# Hive_1_4.net
KiCad netlist of a schematic drawn in EAGLE
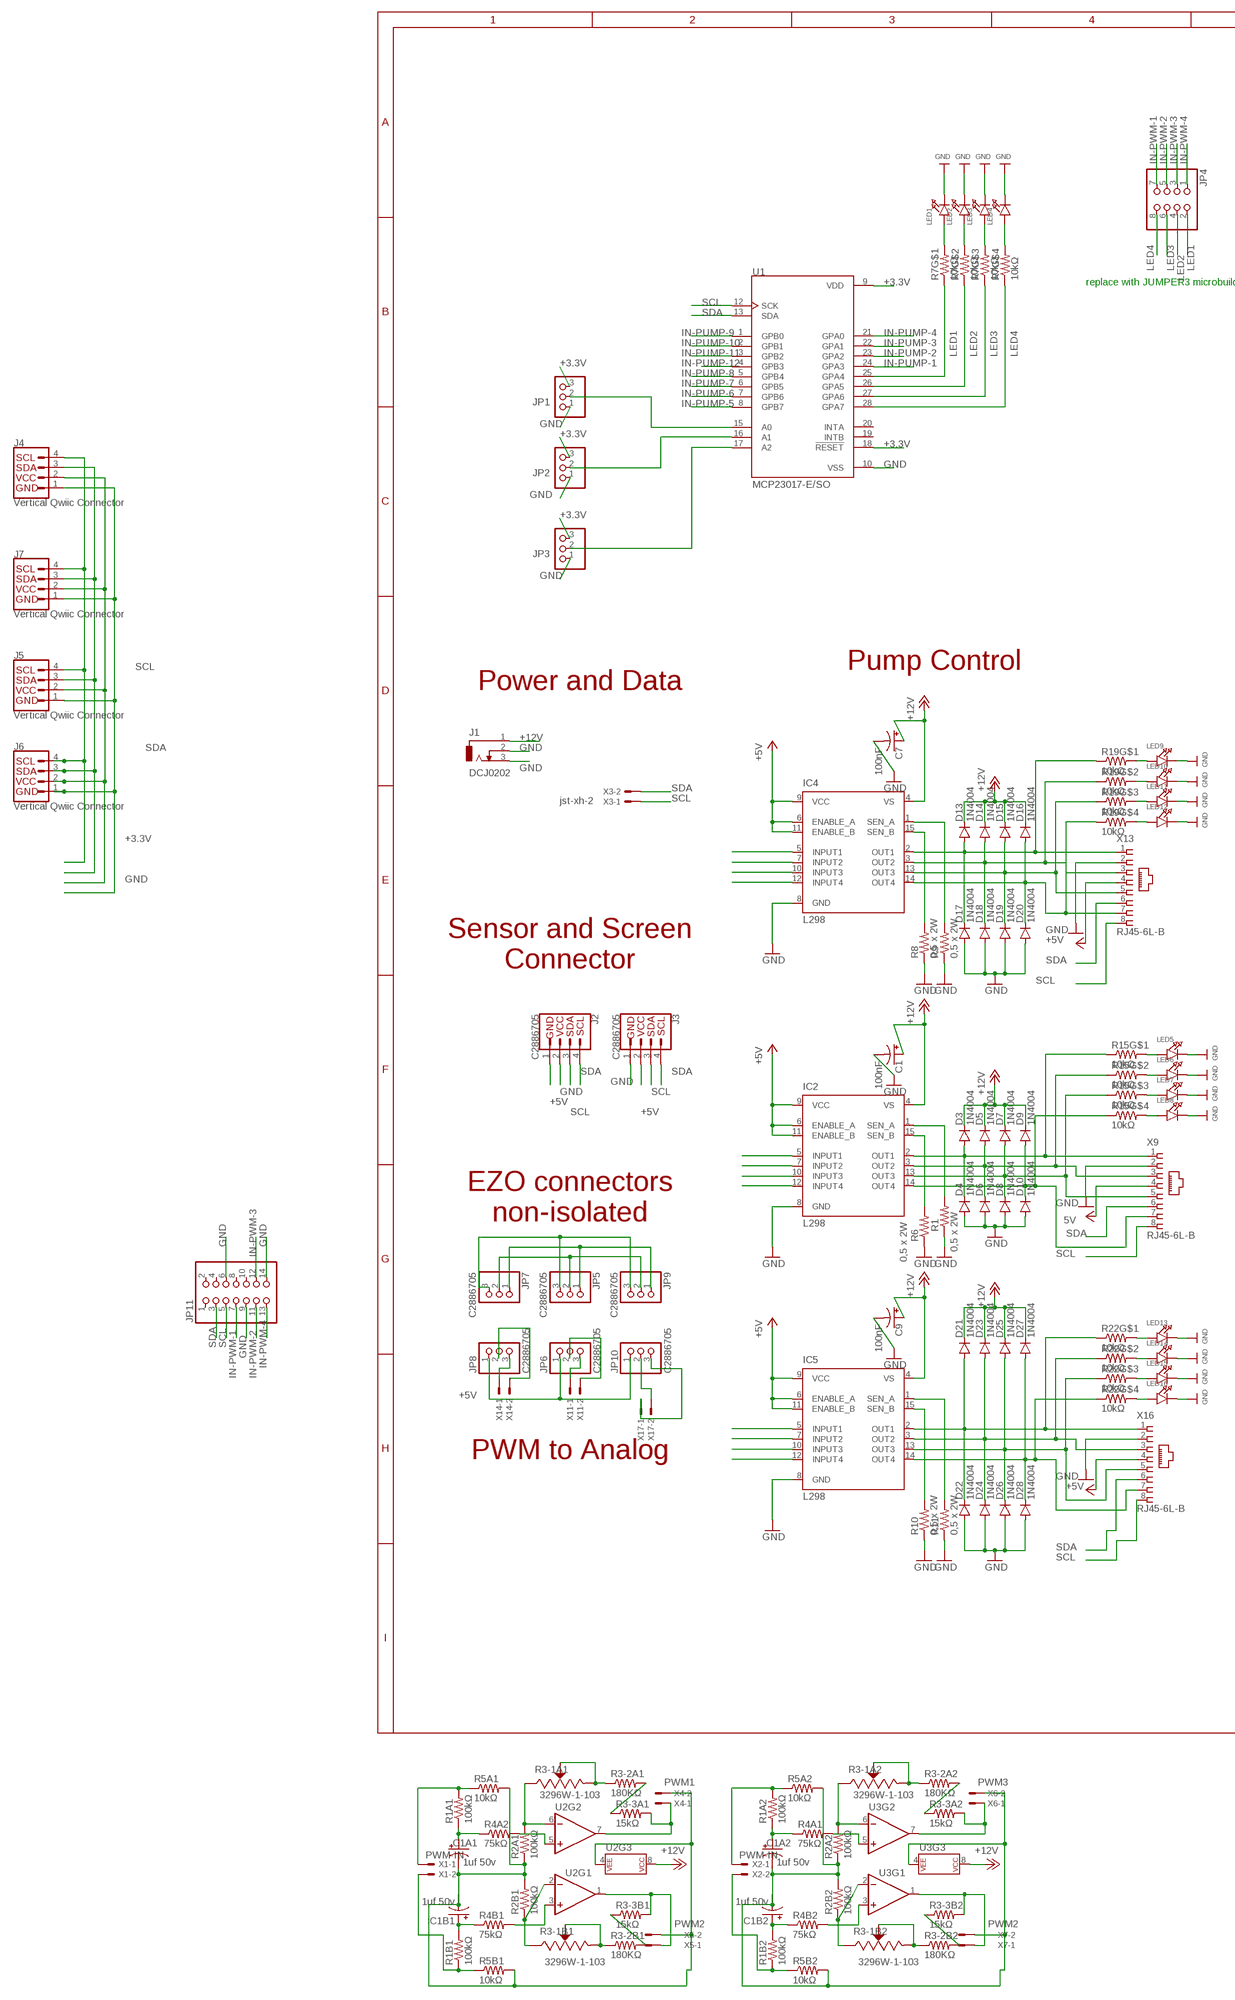
[diagram p0: schematic, sheet 1, part 1 of 2]
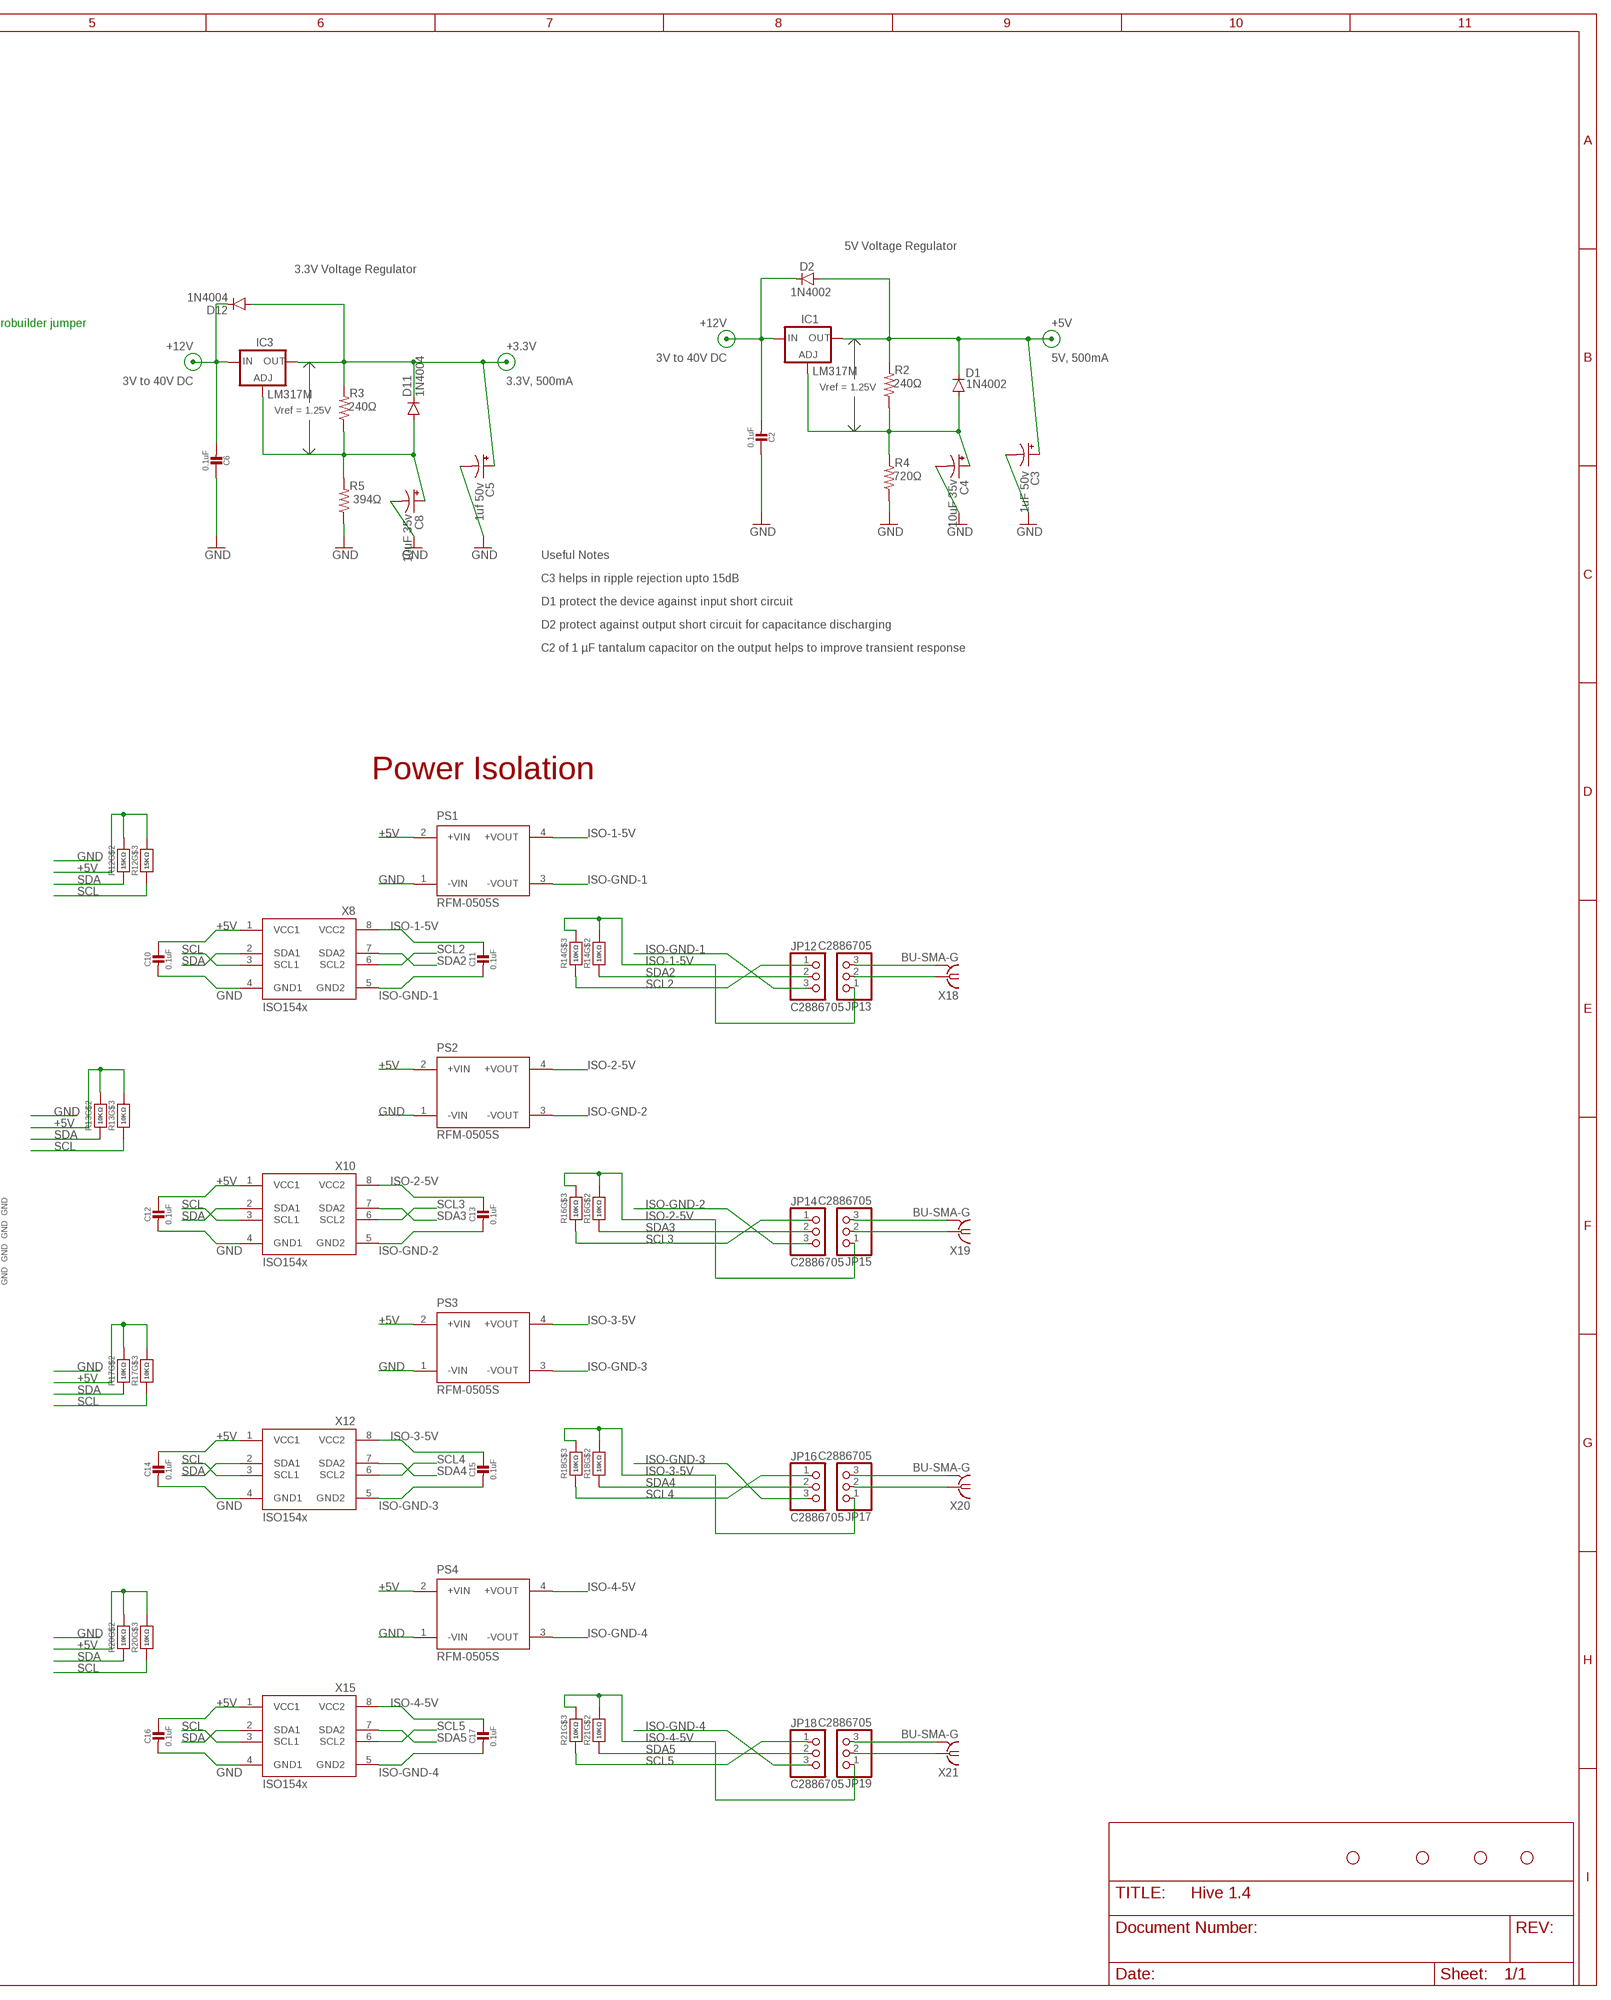
[diagram p1: schematic, sheet 1, part 2 of 2]

(export (version "E")
  (design (tool "Eeschema 10.0.6"))
  (components
    (comp (ref "C1")
      (value "100nF")
      (footprint "eagle-import:UD-4X5,8_NICHICON")
      (libsource (lib "eagle-import") (part "CPOL-USUD-4X5,8"))
    )
    (comp (ref "C1A1")
      (value "1uf 50v")
      (footprint "eagle-import:UD-4X5,8_NICHICON")
      (libsource (lib "eagle-import") (part "CPOL-USUD-4X5,8"))
    )
    (comp (ref "C1A2")
      (value "1uf 50v")
      (footprint "eagle-import:UD-4X5,8_NICHICON")
      (libsource (lib "eagle-import") (part "CPOL-USUD-4X5,8"))
    )
    (comp (ref "C1B1")
      (value "1uf 50v")
      (footprint "eagle-import:UD-4X5,8_NICHICON")
      (libsource (lib "eagle-import") (part "CPOL-USUD-4X5,8"))
    )
    (comp (ref "C1B2")
      (value "1uf 50v")
      (footprint "eagle-import:UD-4X5,8_NICHICON")
      (libsource (lib "eagle-import") (part "CPOL-USUD-4X5,8"))
    )
    (comp (ref "C2")
      (value "0.1uF")
      (footprint "eagle-import:0603-NO")
      (libsource (lib "eagle-import") (part "CAP_CERAMIC0603_NO"))
    )
    (comp (ref "C3")
      (value "1uF 50v")
      (footprint "eagle-import:UD-4X5,8_NICHICON")
      (libsource (lib "eagle-import") (part "CPOL-USUD-4X5,8"))
    )
    (comp (ref "C4")
      (value "10uF 35v")
      (footprint "eagle-import:UD-4X5,8_NICHICON")
      (libsource (lib "eagle-import") (part "CPOL-USUD-4X5,8"))
    )
    (comp (ref "C5")
      (value "1uf 50v")
      (footprint "eagle-import:UD-4X5,8_NICHICON")
      (libsource (lib "eagle-import") (part "CPOL-USUD-4X5,8"))
    )
    (comp (ref "C6")
      (value "0.1uF")
      (footprint "eagle-import:0603-NO")
      (libsource (lib "eagle-import") (part "CAP_CERAMIC0603_NO"))
    )
    (comp (ref "C7")
      (value "100nF")
      (footprint "eagle-import:UD-4X5,8_NICHICON")
      (libsource (lib "eagle-import") (part "CPOL-USUD-4X5,8"))
    )
    (comp (ref "C8")
      (value "10uF 35v")
      (footprint "eagle-import:UD-4X5,8_NICHICON")
      (libsource (lib "eagle-import") (part "CPOL-USUD-4X5,8"))
    )
    (comp (ref "C9")
      (value "100nF")
      (footprint "eagle-import:UD-4X5,8_NICHICON")
      (libsource (lib "eagle-import") (part "CPOL-USUD-4X5,8"))
    )
    (comp (ref "C10")
      (value "0.1uF")
      (footprint "eagle-import:0603-NO")
      (libsource (lib "eagle-import") (part "CAP_CERAMIC0603_NO"))
    )
    (comp (ref "C11")
      (value "0.1uF")
      (footprint "eagle-import:0603-NO")
      (libsource (lib "eagle-import") (part "CAP_CERAMIC0603_NO"))
    )
    (comp (ref "C12")
      (value "0.1uF")
      (footprint "eagle-import:0603-NO")
      (libsource (lib "eagle-import") (part "CAP_CERAMIC0603_NO"))
    )
    (comp (ref "C13")
      (value "0.1uF")
      (footprint "eagle-import:0603-NO")
      (libsource (lib "eagle-import") (part "CAP_CERAMIC0603_NO"))
    )
    (comp (ref "C14")
      (value "0.1uF")
      (footprint "eagle-import:0603-NO")
      (libsource (lib "eagle-import") (part "CAP_CERAMIC0603_NO"))
    )
    (comp (ref "C15")
      (value "0.1uF")
      (footprint "eagle-import:0603-NO")
      (libsource (lib "eagle-import") (part "CAP_CERAMIC0603_NO"))
    )
    (comp (ref "C16")
      (value "0.1uF")
      (footprint "eagle-import:0603-NO")
      (libsource (lib "eagle-import") (part "CAP_CERAMIC0603_NO"))
    )
    (comp (ref "C17")
      (value "0.1uF")
      (footprint "eagle-import:0603-NO")
      (libsource (lib "eagle-import") (part "CAP_CERAMIC0603_NO"))
    )
    (comp (ref "D1")
      (value "1N4002")
      (footprint "eagle-import:DO214BA")
      (libsource (lib "eagle-import") (part "DIODE-DO214BA"))
    )
    (comp (ref "D2")
      (value "1N4002")
      (footprint "eagle-import:DO214BA")
      (libsource (lib "eagle-import") (part "DIODE-DO214BA"))
    )
    (comp (ref "D3")
      (value "1N4004")
      (footprint "eagle-import:DO214BA")
      (libsource (lib "eagle-import") (part "DIODE-DO214BA"))
    )
    (comp (ref "D4")
      (value "1N4004")
      (footprint "eagle-import:DO214BA")
      (libsource (lib "eagle-import") (part "DIODE-DO214BA"))
    )
    (comp (ref "D5")
      (value "1N4004")
      (footprint "eagle-import:DO214BA")
      (libsource (lib "eagle-import") (part "DIODE-DO214BA"))
    )
    (comp (ref "D6")
      (value "1N4004")
      (footprint "eagle-import:DO214BA")
      (libsource (lib "eagle-import") (part "DIODE-DO214BA"))
    )
    (comp (ref "D7")
      (value "1N4004")
      (footprint "eagle-import:DO214BA")
      (libsource (lib "eagle-import") (part "DIODE-DO214BA"))
    )
    (comp (ref "D8")
      (value "1N4004")
      (footprint "eagle-import:DO214BA")
      (libsource (lib "eagle-import") (part "DIODE-DO214BA"))
    )
    (comp (ref "D9")
      (value "1N4004")
      (footprint "eagle-import:DO214BA")
      (libsource (lib "eagle-import") (part "DIODE-DO214BA"))
    )
    (comp (ref "D10")
      (value "1N4004")
      (footprint "eagle-import:DO214BA")
      (libsource (lib "eagle-import") (part "DIODE-DO214BA"))
    )
    (comp (ref "D11")
      (value "1N4004")
      (footprint "eagle-import:DO214BA")
      (libsource (lib "eagle-import") (part "DIODE-DO214BA"))
    )
    (comp (ref "D12")
      (value "1N4004")
      (footprint "eagle-import:DO214BA")
      (libsource (lib "eagle-import") (part "DIODE-DO214BA"))
    )
    (comp (ref "D13")
      (value "1N4004")
      (footprint "eagle-import:DO214BA")
      (libsource (lib "eagle-import") (part "DIODE-DO214BA"))
    )
    (comp (ref "D14")
      (value "1N4004")
      (footprint "eagle-import:DO214BA")
      (libsource (lib "eagle-import") (part "DIODE-DO214BA"))
    )
    (comp (ref "D15")
      (value "1N4004")
      (footprint "eagle-import:DO214BA")
      (libsource (lib "eagle-import") (part "DIODE-DO214BA"))
    )
    (comp (ref "D16")
      (value "1N4004")
      (footprint "eagle-import:DO214BA")
      (libsource (lib "eagle-import") (part "DIODE-DO214BA"))
    )
    (comp (ref "D17")
      (value "1N4004")
      (footprint "eagle-import:DO214BA")
      (libsource (lib "eagle-import") (part "DIODE-DO214BA"))
    )
    (comp (ref "D18")
      (value "1N4004")
      (footprint "eagle-import:DO214BA")
      (libsource (lib "eagle-import") (part "DIODE-DO214BA"))
    )
    (comp (ref "D19")
      (value "1N4004")
      (footprint "eagle-import:DO214BA")
      (libsource (lib "eagle-import") (part "DIODE-DO214BA"))
    )
    (comp (ref "D20")
      (value "1N4004")
      (footprint "eagle-import:DO214BA")
      (libsource (lib "eagle-import") (part "DIODE-DO214BA"))
    )
    (comp (ref "D21")
      (value "1N4004")
      (footprint "eagle-import:DO214BA")
      (libsource (lib "eagle-import") (part "DIODE-DO214BA"))
    )
    (comp (ref "D22")
      (value "1N4004")
      (footprint "eagle-import:DO214BA")
      (libsource (lib "eagle-import") (part "DIODE-DO214BA"))
    )
    (comp (ref "D23")
      (value "1N4004")
      (footprint "eagle-import:DO214BA")
      (libsource (lib "eagle-import") (part "DIODE-DO214BA"))
    )
    (comp (ref "D24")
      (value "1N4004")
      (footprint "eagle-import:DO214BA")
      (libsource (lib "eagle-import") (part "DIODE-DO214BA"))
    )
    (comp (ref "D25")
      (value "1N4004")
      (footprint "eagle-import:DO214BA")
      (libsource (lib "eagle-import") (part "DIODE-DO214BA"))
    )
    (comp (ref "D26")
      (value "1N4004")
      (footprint "eagle-import:DO214BA")
      (libsource (lib "eagle-import") (part "DIODE-DO214BA"))
    )
    (comp (ref "D27")
      (value "1N4004")
      (footprint "eagle-import:DO214BA")
      (libsource (lib "eagle-import") (part "DIODE-DO214BA"))
    )
    (comp (ref "D28")
      (value "1N4004")
      (footprint "eagle-import:DO214BA")
      (libsource (lib "eagle-import") (part "DIODE-DO214BA"))
    )
    (comp (ref "H1")
      (value "STAND-OFF")
      (footprint "eagle-import:STAND-OFF")
      (libsource (lib "eagle-import") (part "STAND-OFF"))
    )
    (comp (ref "H2")
      (value "STAND-OFF")
      (footprint "eagle-import:STAND-OFF")
      (libsource (lib "eagle-import") (part "STAND-OFF"))
    )
    (comp (ref "H3")
      (value "STAND-OFF")
      (footprint "eagle-import:STAND-OFF")
      (libsource (lib "eagle-import") (part "STAND-OFF"))
    )
    (comp (ref "H4")
      (value "STAND-OFF")
      (footprint "eagle-import:STAND-OFF")
      (libsource (lib "eagle-import") (part "STAND-OFF"))
    )
    (comp (ref "IC1")
      (value "LM317MBSTT3")
      (footprint "eagle-import:SOT223")
      (fields (field (name "PARTNUMBER") "LM317M"))
      (libsource (lib "eagle-import") (part "LM317?MBSTT3"))
    )
    (comp (ref "IC2")
      (value "L298")
      (footprint "eagle-import:MULTIWATT-15")
      (fields (field (name "MPN") "L298N"))
      (libsource (lib "eagle-import") (part "L298"))
    )
    (comp (ref "IC3")
      (value "LM317MBSTT3")
      (footprint "eagle-import:SOT223")
      (fields (field (name "PARTNUMBER") "LM317M"))
      (libsource (lib "eagle-import") (part "LM317?MBSTT3"))
    )
    (comp (ref "IC4")
      (value "L298")
      (footprint "eagle-import:MULTIWATT-15")
      (fields (field (name "MPN") "L298N"))
      (libsource (lib "eagle-import") (part "L298"))
    )
    (comp (ref "IC5")
      (value "L298")
      (footprint "eagle-import:MULTIWATT-15")
      (fields (field (name "MPN") "L298N"))
      (libsource (lib "eagle-import") (part "L298"))
    )
    (comp (ref "J1")
      (value "DCJ0202")
      (footprint "eagle-import:DCJ0202")
      (libsource (lib "eagle-import") (part "DCJ0202"))
    )
    (comp (ref "J2")
      (value "C2886705")
      (footprint "eagle-import:1X04")
      (libsource (lib "eagle-import") (part "I2C_STANDARD"))
    )
    (comp (ref "J3")
      (value "C2886705")
      (footprint "eagle-import:1X04")
      (libsource (lib "eagle-import") (part "I2C_STANDARD"))
    )
    (comp (ref "J4")
      (value "Vertical Qwiic Connector")
      (footprint "eagle-import:JST04_1MM_VERT")
      (libsource (lib "eagle-import") (part "QWIIC_CONNECTOR"))
    )
    (comp (ref "J5")
      (value "Vertical Qwiic Connector")
      (footprint "eagle-import:JST04_1MM_VERT")
      (libsource (lib "eagle-import") (part "QWIIC_CONNECTOR"))
    )
    (comp (ref "J6")
      (value "Vertical Qwiic Connector")
      (footprint "eagle-import:JST04_1MM_VERT")
      (libsource (lib "eagle-import") (part "QWIIC_CONNECTOR"))
    )
    (comp (ref "J7")
      (value "Vertical Qwiic Connector")
      (footprint "eagle-import:JST04_1MM_VERT")
      (libsource (lib "eagle-import") (part "QWIIC_CONNECTOR"))
    )
    (comp (ref "JP1")
      (value "HEADER-1X3ROUND")
      (footprint "eagle-import:1X03_ROUND")
      (libsource (lib "eagle-import") (part "HEADER-1X3ROUND"))
    )
    (comp (ref "JP2")
      (value "HEADER-1X3ROUND")
      (footprint "eagle-import:1X03_ROUND")
      (libsource (lib "eagle-import") (part "HEADER-1X3ROUND"))
    )
    (comp (ref "JP3")
      (value "HEADER-1X3ROUND")
      (footprint "eagle-import:1X03_ROUND")
      (libsource (lib "eagle-import") (part "HEADER-1X3ROUND"))
    )
    (comp (ref "JP4")
      (value "PINHD-2X4")
      (footprint "eagle-import:2X04")
      (libsource (lib "eagle-import") (part "PINHD-2X4"))
    )
    (comp (ref "JP5")
      (value "C2886705")
      (footprint "eagle-import:1X03-CLEANBIG")
      (libsource (lib "eagle-import") (part "PINHD-1X3CB"))
    )
    (comp (ref "JP6")
      (value "C2886705")
      (footprint "eagle-import:1X03-CLEANBIG")
      (libsource (lib "eagle-import") (part "PINHD-1X3CB"))
    )
    (comp (ref "JP7")
      (value "C2886705")
      (footprint "eagle-import:1X03-CLEANBIG")
      (libsource (lib "eagle-import") (part "PINHD-1X3CB"))
    )
    (comp (ref "JP8")
      (value "C2886705")
      (footprint "eagle-import:1X03-CLEANBIG")
      (libsource (lib "eagle-import") (part "PINHD-1X3CB"))
    )
    (comp (ref "JP9")
      (value "C2886705")
      (footprint "eagle-import:1X03-CLEANBIG")
      (libsource (lib "eagle-import") (part "PINHD-1X3CB"))
    )
    (comp (ref "JP10")
      (value "C2886705")
      (footprint "eagle-import:1X03-CLEANBIG")
      (libsource (lib "eagle-import") (part "PINHD-1X3CB"))
    )
    (comp (ref "JP11")
      (value "PINHD-2X7")
      (footprint "eagle-import:2X07")
      (libsource (lib "eagle-import") (part "PINHD-2X7"))
    )
    (comp (ref "JP12")
      (value "C2886705")
      (footprint "eagle-import:1X03-CLEANBIG")
      (libsource (lib "eagle-import") (part "PINHD-1X3CB"))
    )
    (comp (ref "JP13")
      (value "C2886705")
      (footprint "eagle-import:1X03-CLEANBIG")
      (libsource (lib "eagle-import") (part "PINHD-1X3CB"))
    )
    (comp (ref "JP14")
      (value "C2886705")
      (footprint "eagle-import:1X03-CLEANBIG")
      (libsource (lib "eagle-import") (part "PINHD-1X3CB"))
    )
    (comp (ref "JP15")
      (value "C2886705")
      (footprint "eagle-import:1X03-CLEANBIG")
      (libsource (lib "eagle-import") (part "PINHD-1X3CB"))
    )
    (comp (ref "JP16")
      (value "C2886705")
      (footprint "eagle-import:1X03-CLEANBIG")
      (libsource (lib "eagle-import") (part "PINHD-1X3CB"))
    )
    (comp (ref "JP17")
      (value "C2886705")
      (footprint "eagle-import:1X03-CLEANBIG")
      (libsource (lib "eagle-import") (part "PINHD-1X3CB"))
    )
    (comp (ref "JP18")
      (value "C2886705")
      (footprint "eagle-import:1X03-CLEANBIG")
      (libsource (lib "eagle-import") (part "PINHD-1X3CB"))
    )
    (comp (ref "JP19")
      (value "C2886705")
      (footprint "eagle-import:1X03-CLEANBIG")
      (libsource (lib "eagle-import") (part "PINHD-1X3CB"))
    )
    (comp (ref "LED1")
      (value "LED0603")
      (footprint "eagle-import:CHIPLED_0603")
      (libsource (lib "eagle-import") (part "LED0603"))
    )
    (comp (ref "LED2")
      (value "LED0603")
      (footprint "eagle-import:CHIPLED_0603")
      (libsource (lib "eagle-import") (part "LED0603"))
    )
    (comp (ref "LED3")
      (value "LED0603")
      (footprint "eagle-import:CHIPLED_0603")
      (libsource (lib "eagle-import") (part "LED0603"))
    )
    (comp (ref "LED4")
      (value "LED0603")
      (footprint "eagle-import:CHIPLED_0603")
      (libsource (lib "eagle-import") (part "LED0603"))
    )
    (comp (ref "LED5")
      (value "LED0603")
      (footprint "eagle-import:CHIPLED_0603")
      (libsource (lib "eagle-import") (part "LED0603"))
    )
    (comp (ref "LED6")
      (value "LED0603")
      (footprint "eagle-import:CHIPLED_0603")
      (libsource (lib "eagle-import") (part "LED0603"))
    )
    (comp (ref "LED7")
      (value "LED0603")
      (footprint "eagle-import:CHIPLED_0603")
      (libsource (lib "eagle-import") (part "LED0603"))
    )
    (comp (ref "LED8")
      (value "LED0603")
      (footprint "eagle-import:CHIPLED_0603")
      (libsource (lib "eagle-import") (part "LED0603"))
    )
    (comp (ref "LED9")
      (value "LED0603")
      (footprint "eagle-import:CHIPLED_0603")
      (libsource (lib "eagle-import") (part "LED0603"))
    )
    (comp (ref "LED10")
      (value "LED0603")
      (footprint "eagle-import:CHIPLED_0603")
      (libsource (lib "eagle-import") (part "LED0603"))
    )
    (comp (ref "LED11")
      (value "LED0603")
      (footprint "eagle-import:CHIPLED_0603")
      (libsource (lib "eagle-import") (part "LED0603"))
    )
    (comp (ref "LED12")
      (value "LED0603")
      (footprint "eagle-import:CHIPLED_0603")
      (libsource (lib "eagle-import") (part "LED0603"))
    )
    (comp (ref "LED13")
      (value "LED0603")
      (footprint "eagle-import:CHIPLED_0603")
      (libsource (lib "eagle-import") (part "LED0603"))
    )
    (comp (ref "LED14")
      (value "LED0603")
      (footprint "eagle-import:CHIPLED_0603")
      (libsource (lib "eagle-import") (part "LED0603"))
    )
    (comp (ref "LED15")
      (value "LED0603")
      (footprint "eagle-import:CHIPLED_0603")
      (libsource (lib "eagle-import") (part "LED0603"))
    )
    (comp (ref "LED16")
      (value "LED0603")
      (footprint "eagle-import:CHIPLED_0603")
      (libsource (lib "eagle-import") (part "LED0603"))
    )
    (comp (ref "PS1")
      (value "RFM-0505S")
      (footprint "eagle-import:CONV_RFM-0505S")
      (fields (field (name "MF") "Recom Power"))
      (libsource (lib "eagle-import") (part "RFM-0505S"))
    )
    (comp (ref "PS2")
      (value "RFM-0505S")
      (footprint "eagle-import:CONV_RFM-0505S")
      (fields (field (name "MF") "Recom Power"))
      (libsource (lib "eagle-import") (part "RFM-0505S"))
    )
    (comp (ref "PS3")
      (value "RFM-0505S")
      (footprint "eagle-import:CONV_RFM-0505S")
      (fields (field (name "MF") "Recom Power"))
      (libsource (lib "eagle-import") (part "RFM-0505S"))
    )
    (comp (ref "PS4")
      (value "RFM-0505S")
      (footprint "eagle-import:CONV_RFM-0505S")
      (fields (field (name "MF") "Recom Power"))
      (libsource (lib "eagle-import") (part "RFM-0505S"))
    )
    (comp (ref "R1")
      (value "0,5 x 2W")
      (footprint "eagle-import:R2512")
      (libsource (lib "eagle-import") (part "R-US_R2512"))
    )
    (comp (ref "R1A1")
      (value "100kΩ")
      (footprint "eagle-import:M1206")
      (libsource (lib "eagle-import") (part "adafruit_420_R-US_M1206"))
    )
    (comp (ref "R1A2")
      (value "100kΩ")
      (footprint "eagle-import:M1206")
      (libsource (lib "eagle-import") (part "adafruit_420_R-US_M1206"))
    )
    (comp (ref "R1B1")
      (value "100kΩ")
      (footprint "eagle-import:M1206")
      (libsource (lib "eagle-import") (part "adafruit_420_R-US_M1206"))
    )
    (comp (ref "R1B2")
      (value "100kΩ")
      (footprint "eagle-import:M1206")
      (libsource (lib "eagle-import") (part "adafruit_420_R-US_M1206"))
    )
    (comp (ref "R2")
      (value "240Ω")
      (footprint "eagle-import:M0805")
      (libsource (lib "eagle-import") (part "resistor_R-US_M0805"))
    )
    (comp (ref "R2A1")
      (value "100kΩ")
      (footprint "eagle-import:M1206")
      (libsource (lib "eagle-import") (part "adafruit_420_R-US_M1206"))
    )
    (comp (ref "R2A2")
      (value "100kΩ")
      (footprint "eagle-import:M1206")
      (libsource (lib "eagle-import") (part "adafruit_420_R-US_M1206"))
    )
    (comp (ref "R2B1")
      (value "100kΩ")
      (footprint "eagle-import:M1206")
      (libsource (lib "eagle-import") (part "adafruit_420_R-US_M1206"))
    )
    (comp (ref "R2B2")
      (value "100kΩ")
      (footprint "eagle-import:M1206")
      (libsource (lib "eagle-import") (part "adafruit_420_R-US_M1206"))
    )
    (comp (ref "R3")
      (value "240Ω")
      (footprint "eagle-import:M0805")
      (libsource (lib "eagle-import") (part "resistor_R-US_M0805"))
    )
    (comp (ref "R3-1A1")
      (value "3296W-1-103")
      (footprint "eagle-import:TRIM_3296W-1-103")
      (fields (field (name "MF") "Bourns"))
      (libsource (lib "eagle-import") (part "3296W-1-103"))
    )
    (comp (ref "R3-1A2")
      (value "3296W-1-103")
      (footprint "eagle-import:TRIM_3296W-1-103")
      (fields (field (name "MF") "Bourns"))
      (libsource (lib "eagle-import") (part "3296W-1-103"))
    )
    (comp (ref "R3-1B1")
      (value "3296W-1-103")
      (footprint "eagle-import:TRIM_3296W-1-103")
      (fields (field (name "MF") "Bourns"))
      (libsource (lib "eagle-import") (part "3296W-1-103"))
    )
    (comp (ref "R3-1B2")
      (value "3296W-1-103")
      (footprint "eagle-import:TRIM_3296W-1-103")
      (fields (field (name "MF") "Bourns"))
      (libsource (lib "eagle-import") (part "3296W-1-103"))
    )
    (comp (ref "R3-2A1")
      (value "180KΩ")
      (footprint "eagle-import:M1206")
      (libsource (lib "eagle-import") (part "adafruit_420_R-US_M1206"))
    )
    (comp (ref "R3-2A2")
      (value "180KΩ")
      (footprint "eagle-import:M1206")
      (libsource (lib "eagle-import") (part "adafruit_420_R-US_M1206"))
    )
    (comp (ref "R3-2B1")
      (value "180KΩ")
      (footprint "eagle-import:M1206")
      (libsource (lib "eagle-import") (part "adafruit_420_R-US_M1206"))
    )
    (comp (ref "R3-2B2")
      (value "180KΩ")
      (footprint "eagle-import:M1206")
      (libsource (lib "eagle-import") (part "adafruit_420_R-US_M1206"))
    )
    (comp (ref "R3-3A1")
      (value "15kΩ")
      (footprint "eagle-import:M1206")
      (libsource (lib "eagle-import") (part "adafruit_420_R-US_M1206"))
    )
    (comp (ref "R3-3A2")
      (value "15kΩ")
      (footprint "eagle-import:M1206")
      (libsource (lib "eagle-import") (part "adafruit_420_R-US_M1206"))
    )
    (comp (ref "R3-3B1")
      (value "15kΩ")
      (footprint "eagle-import:M1206")
      (libsource (lib "eagle-import") (part "adafruit_420_R-US_M1206"))
    )
    (comp (ref "R3-3B2")
      (value "15kΩ")
      (footprint "eagle-import:M1206")
      (libsource (lib "eagle-import") (part "adafruit_420_R-US_M1206"))
    )
    (comp (ref "R4")
      (value "720Ω")
      (footprint "eagle-import:M0805")
      (libsource (lib "eagle-import") (part "resistor_R-US_M0805"))
    )
    (comp (ref "R4A1")
      (value "75kΩ")
      (footprint "eagle-import:M1206")
      (libsource (lib "eagle-import") (part "adafruit_420_R-US_M1206"))
    )
    (comp (ref "R4A2")
      (value "75kΩ")
      (footprint "eagle-import:M1206")
      (libsource (lib "eagle-import") (part "adafruit_420_R-US_M1206"))
    )
    (comp (ref "R4B1")
      (value "75kΩ")
      (footprint "eagle-import:M1206")
      (libsource (lib "eagle-import") (part "adafruit_420_R-US_M1206"))
    )
    (comp (ref "R4B2")
      (value "75kΩ")
      (footprint "eagle-import:M1206")
      (libsource (lib "eagle-import") (part "adafruit_420_R-US_M1206"))
    )
    (comp (ref "R5")
      (value "394Ω")
      (footprint "eagle-import:M0805")
      (libsource (lib "eagle-import") (part "resistor_R-US_M0805"))
    )
    (comp (ref "R5A1")
      (value "10kΩ")
      (footprint "eagle-import:M1206")
      (libsource (lib "eagle-import") (part "adafruit_420_R-US_M1206"))
    )
    (comp (ref "R5A2")
      (value "10kΩ")
      (footprint "eagle-import:M1206")
      (libsource (lib "eagle-import") (part "adafruit_420_R-US_M1206"))
    )
    (comp (ref "R5B1")
      (value "10kΩ")
      (footprint "eagle-import:M1206")
      (libsource (lib "eagle-import") (part "adafruit_420_R-US_M1206"))
    )
    (comp (ref "R5B2")
      (value "10kΩ")
      (footprint "eagle-import:M1206")
      (libsource (lib "eagle-import") (part "adafruit_420_R-US_M1206"))
    )
    (comp (ref "R6")
      (value "0,5 x 2W")
      (footprint "eagle-import:R2512")
      (libsource (lib "eagle-import") (part "R-US_R2512"))
    )
    (comp (ref "R7")
      (value "10kΩ")
      (footprint "eagle-import:RESPACK_4X0603")
      (libsource (lib "eagle-import") (part "RESISTOR_4PACK_US"))
    )
    (comp (ref "R8")
      (value "0,5 x 2W")
      (footprint "eagle-import:R2512")
      (libsource (lib "eagle-import") (part "R-US_R2512"))
    )
    (comp (ref "R9")
      (value "0,5 x 2W")
      (footprint "eagle-import:R2512")
      (libsource (lib "eagle-import") (part "R-US_R2512"))
    )
    (comp (ref "R10")
      (value "0,5 x 2W")
      (footprint "eagle-import:R2512")
      (libsource (lib "eagle-import") (part "R-US_R2512"))
    )
    (comp (ref "R11")
      (value "0,5 x 2W")
      (footprint "eagle-import:R2512")
      (libsource (lib "eagle-import") (part "R-US_R2512"))
    )
    (comp (ref "R12")
      (value "15KΩ")
      (footprint "eagle-import:RESPACK_4X0603")
      (libsource (lib "eagle-import") (part "RESISTOR_4PACK"))
    )
    (comp (ref "R13")
      (value "10KΩ")
      (footprint "eagle-import:RESPACK_4X0603")
      (libsource (lib "eagle-import") (part "RESISTOR_4PACK"))
    )
    (comp (ref "R14")
      (value "10KΩ")
      (footprint "eagle-import:RESPACK_4X0603")
      (libsource (lib "eagle-import") (part "RESISTOR_4PACK"))
    )
    (comp (ref "R15")
      (value "10kΩ")
      (footprint "eagle-import:RESPACK_4X0603")
      (libsource (lib "eagle-import") (part "RESISTOR_4PACK_US"))
    )
    (comp (ref "R16")
      (value "10KΩ")
      (footprint "eagle-import:RESPACK_4X0603")
      (libsource (lib "eagle-import") (part "RESISTOR_4PACK"))
    )
    (comp (ref "R17")
      (value "10KΩ")
      (footprint "eagle-import:RESPACK_4X0603")
      (libsource (lib "eagle-import") (part "RESISTOR_4PACK"))
    )
    (comp (ref "R18")
      (value "10KΩ")
      (footprint "eagle-import:RESPACK_4X0603")
      (libsource (lib "eagle-import") (part "RESISTOR_4PACK"))
    )
    (comp (ref "R19")
      (value "10kΩ")
      (footprint "eagle-import:RESPACK_4X0603")
      (libsource (lib "eagle-import") (part "RESISTOR_4PACK_US"))
    )
    (comp (ref "R20")
      (value "10KΩ")
      (footprint "eagle-import:RESPACK_4X0603")
      (libsource (lib "eagle-import") (part "RESISTOR_4PACK"))
    )
    (comp (ref "R21")
      (value "10KΩ")
      (footprint "eagle-import:RESPACK_4X0603")
      (libsource (lib "eagle-import") (part "RESISTOR_4PACK"))
    )
    (comp (ref "R22")
      (value "10kΩ")
      (footprint "eagle-import:RESPACK_4X0603")
      (libsource (lib "eagle-import") (part "RESISTOR_4PACK_US"))
    )
    (comp (ref "U1")
      (value "MCP23017-E/SO")
      (footprint "eagle-import:SOIC127P1030X265-28N")
      (fields (field (name "MF") "Microchip"))
      (libsource (lib "eagle-import") (part "MCP23017-E/SO"))
    )
    (comp (ref "U2")
      (value "LM358")
      (footprint "eagle-import:SO08")
      (libsource (lib "eagle-import") (part "LM358SO08"))
    )
    (comp (ref "U3")
      (value "LM358")
      (footprint "eagle-import:SO08")
      (libsource (lib "eagle-import") (part "LM358SO08"))
    )
    (comp (ref "X1")
      (value "PWM-IN")
      (footprint "eagle-import:JST-XH-02-PACKAGE-LONG-PAD")
      (libsource (lib "eagle-import") (part "JST-XH-02-PIN-LONG-PAD"))
    )
    (comp (ref "X2")
      (value "PWM-IN")
      (footprint "eagle-import:JST-XH-02-PACKAGE-LONG-PAD")
      (libsource (lib "eagle-import") (part "JST-XH-02-PIN-LONG-PAD"))
    )
    (comp (ref "X3")
      (value "jst-xh-2")
      (footprint "eagle-import:JST-XH-02-PACKAGE-LONG-PAD")
      (libsource (lib "eagle-import") (part "JST-XH-02-PIN-LONG-PAD"))
    )
    (comp (ref "X4")
      (value "PWM1")
      (footprint "eagle-import:JST-XH-02-PACKAGE-LONG-PAD")
      (libsource (lib "eagle-import") (part "JST-XH-02-PIN-LONG-PAD"))
    )
    (comp (ref "X5")
      (value "PWM2")
      (footprint "eagle-import:JST-XH-02-PACKAGE-LONG-PAD")
      (libsource (lib "eagle-import") (part "JST-XH-02-PIN-LONG-PAD"))
    )
    (comp (ref "X6")
      (value "PWM3")
      (footprint "eagle-import:JST-XH-02-PACKAGE-LONG-PAD")
      (libsource (lib "eagle-import") (part "JST-XH-02-PIN-LONG-PAD"))
    )
    (comp (ref "X7")
      (value "PWM2")
      (footprint "eagle-import:JST-XH-02-PACKAGE-LONG-PAD")
      (libsource (lib "eagle-import") (part "JST-XH-02-PIN-LONG-PAD"))
    )
    (comp (ref "X8")
      (value "ISO154X")
      (footprint "eagle-import:SOIC8_150MIL")
      (libsource (lib "eagle-import") (part "ISO154X"))
    )
    (comp (ref "X9")
      (value "RJ45-6L-B")
      (footprint "eagle-import:RJ45-NO-SHIELD")
      (libsource (lib "eagle-import") (part "RJ45-6L-B"))
    )
    (comp (ref "X10")
      (value "ISO154X")
      (footprint "eagle-import:SOIC8_150MIL")
      (libsource (lib "eagle-import") (part "ISO154X"))
    )
    (comp (ref "X11")
      (value "jst-xh-2")
      (footprint "eagle-import:JST-XH-02-PACKAGE-LONG-PAD")
      (libsource (lib "eagle-import") (part "JST-XH-02-PIN-LONG-PAD"))
    )
    (comp (ref "X12")
      (value "ISO154X")
      (footprint "eagle-import:SOIC8_150MIL")
      (libsource (lib "eagle-import") (part "ISO154X"))
    )
    (comp (ref "X13")
      (value "RJ45-6L-B")
      (footprint "eagle-import:RJ45-NO-SHIELD")
      (libsource (lib "eagle-import") (part "RJ45-6L-B"))
    )
    (comp (ref "X14")
      (value "jst-xh-2")
      (footprint "eagle-import:JST-XH-02-PACKAGE-LONG-PAD")
      (libsource (lib "eagle-import") (part "JST-XH-02-PIN-LONG-PAD"))
    )
    (comp (ref "X15")
      (value "ISO154X")
      (footprint "eagle-import:SOIC8_150MIL")
      (libsource (lib "eagle-import") (part "ISO154X"))
    )
    (comp (ref "X16")
      (value "RJ45-6L-B")
      (footprint "eagle-import:RJ45-NO-SHIELD")
      (libsource (lib "eagle-import") (part "RJ45-6L-B"))
    )
    (comp (ref "X17")
      (value "jst-xh-2")
      (footprint "eagle-import:JST-XH-02-PACKAGE-LONG-PAD")
      (libsource (lib "eagle-import") (part "JST-XH-02-PIN-LONG-PAD"))
    )
    (comp (ref "X18")
      (value "BU-SMA-G")
      (footprint "eagle-import:BU-SMA-G")
      (libsource (lib "eagle-import") (part "BU-SMA-G"))
    )
    (comp (ref "X19")
      (value "BU-SMA-G")
      (footprint "eagle-import:BU-SMA-G")
      (libsource (lib "eagle-import") (part "BU-SMA-G"))
    )
    (comp (ref "X20")
      (value "BU-SMA-G")
      (footprint "eagle-import:BU-SMA-G")
      (libsource (lib "eagle-import") (part "BU-SMA-G"))
    )
    (comp (ref "X21")
      (value "BU-SMA-G")
      (footprint "eagle-import:BU-SMA-G")
      (libsource (lib "eagle-import") (part "BU-SMA-G"))
    )
  )
  (nets
    (net (code "1") (name "+3V3") (class "Default")
      (node (ref "C10") (pin "1") (pinfunction "1_1") (pintype "passive"))
      (node (ref "C12") (pin "1") (pinfunction "1_1") (pintype "passive"))
      (node (ref "C14") (pin "1") (pinfunction "1_1") (pintype "passive"))
      (node (ref "C16") (pin "1") (pinfunction "1_1") (pintype "passive"))
      (node (ref "C3") (pin "+") (pinfunction "+_+") (pintype "passive"))
      (node (ref "D1") (pin "C") (pinfunction "C_C") (pintype "passive"))
      (node (ref "D2") (pin "A") (pinfunction "A_A") (pintype "passive"))
      (node (ref "IC1") (pin "4") (pinfunction "OUT_4") (pintype "passive"))
      (node (ref "IC2") (pin "11") (pinfunction "ENABLE_B_11") (pintype "input"))
      (node (ref "IC2") (pin "6") (pinfunction "ENABLE_A_6") (pintype "input"))
      (node (ref "IC2") (pin "9") (pinfunction "VCC_9") (pintype "power_in"))
      (node (ref "IC4") (pin "11") (pinfunction "ENABLE_B_11") (pintype "input"))
      (node (ref "IC4") (pin "6") (pinfunction "ENABLE_A_6") (pintype "input"))
      (node (ref "IC4") (pin "9") (pinfunction "VCC_9") (pintype "power_in"))
      (node (ref "IC5") (pin "11") (pinfunction "ENABLE_B_11") (pintype "input"))
      (node (ref "IC5") (pin "6") (pinfunction "ENABLE_A_6") (pintype "input"))
      (node (ref "IC5") (pin "9") (pinfunction "VCC_9") (pintype "power_in"))
      (node (ref "J2") (pin "1") (pinfunction "1_1") (pintype "power_in"))
      (node (ref "J3") (pin "2") (pinfunction "2_2") (pintype "power_in"))
      (node (ref "JP10") (pin "1") (pinfunction "1_1") (pintype "passive"))
      (node (ref "JP6") (pin "1") (pinfunction "1_1") (pintype "passive"))
      (node (ref "JP8") (pin "1") (pinfunction "1_1") (pintype "passive"))
      (node (ref "PS1") (pin "2") (pinfunction "+VIN_2") (pintype "input"))
      (node (ref "PS2") (pin "2") (pinfunction "+VIN_2") (pintype "input"))
      (node (ref "PS3") (pin "2") (pinfunction "+VIN_2") (pintype "input"))
      (node (ref "PS4") (pin "2") (pinfunction "+VIN_2") (pintype "input"))
      (node (ref "R12") (pin "6") (pinfunction "2_6") (pintype "passive"))
      (node (ref "R12") (pin "7") (pinfunction "2_7") (pintype "passive"))
      (node (ref "R13") (pin "6") (pinfunction "2_6") (pintype "passive"))
      (node (ref "R13") (pin "7") (pinfunction "2_7") (pintype "passive"))
      (node (ref "R17") (pin "6") (pinfunction "2_6") (pintype "passive"))
      (node (ref "R17") (pin "7") (pinfunction "2_7") (pintype "passive"))
      (node (ref "R2") (pin "2") (pinfunction "2_2") (pintype "passive"))
      (node (ref "R20") (pin "6") (pinfunction "2_6") (pintype "passive"))
      (node (ref "R20") (pin "7") (pinfunction "2_7") (pintype "passive"))
      (node (ref "X10") (pin "1") (pinfunction "VCC1_1") (pintype "power_in"))
      (node (ref "X12") (pin "1") (pinfunction "VCC1_1") (pintype "power_in"))
      (node (ref "X13") (pin "4") (pinfunction "4_4") (pintype "passive"))
      (node (ref "X15") (pin "1") (pinfunction "VCC1_1") (pintype "power_in"))
      (node (ref "X16") (pin "4") (pinfunction "4_4") (pintype "passive"))
      (node (ref "X8") (pin "1") (pinfunction "VCC1_1") (pintype "power_in"))
      (node (ref "X9") (pin "4") (pinfunction "4_4") (pintype "passive"))
    )
    (net (code "2") (name "+12V") (class "Default")
      (node (ref "C1") (pin "+") (pinfunction "+_+") (pintype "passive"))
      (node (ref "C2") (pin "2") (pinfunction "2_2") (pintype "passive"))
      (node (ref "C6") (pin "2") (pinfunction "2_2") (pintype "passive"))
      (node (ref "C7") (pin "+") (pinfunction "+_+") (pintype "passive"))
      (node (ref "C9") (pin "+") (pinfunction "+_+") (pintype "passive"))
      (node (ref "D12") (pin "C") (pinfunction "C_C") (pintype "passive"))
      (node (ref "D13") (pin "C") (pinfunction "C_C") (pintype "passive"))
      (node (ref "D14") (pin "C") (pinfunction "C_C") (pintype "passive"))
      (node (ref "D15") (pin "C") (pinfunction "C_C") (pintype "passive"))
      (node (ref "D16") (pin "C") (pinfunction "C_C") (pintype "passive"))
      (node (ref "D2") (pin "C") (pinfunction "C_C") (pintype "passive"))
      (node (ref "D21") (pin "C") (pinfunction "C_C") (pintype "passive"))
      (node (ref "D23") (pin "C") (pinfunction "C_C") (pintype "passive"))
      (node (ref "D25") (pin "C") (pinfunction "C_C") (pintype "passive"))
      (node (ref "D27") (pin "C") (pinfunction "C_C") (pintype "passive"))
      (node (ref "D3") (pin "C") (pinfunction "C_C") (pintype "passive"))
      (node (ref "D5") (pin "C") (pinfunction "C_C") (pintype "passive"))
      (node (ref "D7") (pin "C") (pinfunction "C_C") (pintype "passive"))
      (node (ref "D9") (pin "C") (pinfunction "C_C") (pintype "passive"))
      (node (ref "IC1") (pin "3") (pinfunction "IN_3") (pintype "input"))
      (node (ref "IC2") (pin "4") (pinfunction "VS_4") (pintype "power_in"))
      (node (ref "IC3") (pin "3") (pinfunction "IN_3") (pintype "input"))
      (node (ref "IC4") (pin "4") (pinfunction "VS_4") (pintype "power_in"))
      (node (ref "IC5") (pin "4") (pinfunction "VS_4") (pintype "power_in"))
      (node (ref "J1") (pin "1") (pinfunction "1_1") (pintype "passive"))
      (node (ref "U2") (pin "8") (pinfunction "P$V+_8") (pintype "bidirectional"))
      (node (ref "U3") (pin "8") (pinfunction "P$V+_8") (pintype "bidirectional"))
    )
    (net (code "3") (name "/+3.3V") (class "Default")
      (node (ref "C5") (pin "+") (pinfunction "+_+") (pintype "passive"))
      (node (ref "D11") (pin "C") (pinfunction "C_C") (pintype "passive"))
      (node (ref "D12") (pin "A") (pinfunction "A_A") (pintype "passive"))
      (node (ref "IC3") (pin "4") (pinfunction "OUT_4") (pintype "passive"))
      (node (ref "J4") (pin "2") (pinfunction "2_2") (pintype "power_in"))
      (node (ref "J5") (pin "2") (pinfunction "2_2") (pintype "power_in"))
      (node (ref "J6") (pin "2") (pinfunction "2_2") (pintype "power_in"))
      (node (ref "J7") (pin "2") (pinfunction "2_2") (pintype "power_in"))
      (node (ref "JP1") (pin "3") (pinfunction "3_3") (pintype "passive"))
      (node (ref "JP2") (pin "3") (pinfunction "3_3") (pintype "passive"))
      (node (ref "JP3") (pin "3") (pinfunction "3_3") (pintype "passive"))
      (node (ref "R3") (pin "2") (pinfunction "2_2") (pintype "passive"))
      (node (ref "U1") (pin "18") (pinfunction "~{RESET}_18") (pintype "output"))
      (node (ref "U1") (pin "9") (pinfunction "VDD_9") (pintype "power_in"))
    )
    (net (code "4") (name "/IN-PUMP-1") (class "Default")
      (node (ref "IC2") (pin "5") (pinfunction "INPUT1_5") (pintype "input"))
      (node (ref "U1") (pin "24") (pinfunction "GPA3_24") (pintype "bidirectional"))
    )
    (net (code "5") (name "/IN-PUMP-2") (class "Default")
      (node (ref "IC2") (pin "7") (pinfunction "INPUT2_7") (pintype "input"))
      (node (ref "U1") (pin "23") (pinfunction "GPA2_23") (pintype "bidirectional"))
    )
    (net (code "6") (name "/IN-PUMP-3") (class "Default")
      (node (ref "IC2") (pin "10") (pinfunction "INPUT3_10") (pintype "input"))
      (node (ref "U1") (pin "22") (pinfunction "GPA1_22") (pintype "bidirectional"))
    )
    (net (code "7") (name "/IN-PUMP-4") (class "Default")
      (node (ref "IC2") (pin "12") (pinfunction "INPUT4_12") (pintype "input"))
      (node (ref "U1") (pin "21") (pinfunction "GPA0_21") (pintype "bidirectional"))
    )
    (net (code "8") (name "/IN-PUMP-5") (class "Default")
      (node (ref "IC4") (pin "5") (pinfunction "INPUT1_5") (pintype "input"))
      (node (ref "U1") (pin "8") (pinfunction "GPB7_8") (pintype "bidirectional"))
    )
    (net (code "9") (name "/IN-PUMP-6") (class "Default")
      (node (ref "IC4") (pin "7") (pinfunction "INPUT2_7") (pintype "input"))
      (node (ref "U1") (pin "7") (pinfunction "GPB6_7") (pintype "bidirectional"))
    )
    (net (code "10") (name "/IN-PUMP-7") (class "Default")
      (node (ref "IC4") (pin "10") (pinfunction "INPUT3_10") (pintype "input"))
      (node (ref "U1") (pin "6") (pinfunction "GPB5_6") (pintype "bidirectional"))
    )
    (net (code "11") (name "/IN-PUMP-8") (class "Default")
      (node (ref "IC4") (pin "12") (pinfunction "INPUT4_12") (pintype "input"))
      (node (ref "U1") (pin "5") (pinfunction "GPB4_5") (pintype "bidirectional"))
    )
    (net (code "12") (name "/IN-PUMP-9") (class "Default")
      (node (ref "IC5") (pin "5") (pinfunction "INPUT1_5") (pintype "input"))
      (node (ref "U1") (pin "1") (pinfunction "GPB0_1") (pintype "bidirectional"))
    )
    (net (code "13") (name "/IN-PUMP-10") (class "Default")
      (node (ref "IC5") (pin "7") (pinfunction "INPUT2_7") (pintype "input"))
      (node (ref "U1") (pin "2") (pinfunction "GPB1_2") (pintype "bidirectional"))
    )
    (net (code "14") (name "/IN-PUMP-11") (class "Default")
      (node (ref "IC5") (pin "10") (pinfunction "INPUT3_10") (pintype "input"))
      (node (ref "U1") (pin "3") (pinfunction "GPB2_3") (pintype "bidirectional"))
    )
    (net (code "15") (name "/IN-PUMP-12") (class "Default")
      (node (ref "IC5") (pin "12") (pinfunction "INPUT4_12") (pintype "input"))
      (node (ref "U1") (pin "4") (pinfunction "GPB3_4") (pintype "bidirectional"))
    )
    (net (code "16") (name "/IN-PWM-1") (class "Default")
      (node (ref "JP11") (pin "7") (pinfunction "7_7") (pintype "passive"))
      (node (ref "JP4") (pin "7") (pinfunction "7_7") (pintype "passive"))
      (node (ref "R1A1") (pin "2") (pinfunction "2_2") (pintype "passive"))
      (node (ref "R5A1") (pin "1") (pinfunction "1_1") (pintype "passive"))
      (node (ref "X1") (pin "1") (pinfunction "S_1") (pintype "passive"))
    )
    (net (code "17") (name "/IN-PWM-2") (class "Default")
      (node (ref "JP11") (pin "11") (pinfunction "11_11") (pintype "passive"))
      (node (ref "JP4") (pin "5") (pinfunction "5_5") (pintype "passive"))
      (node (ref "R1B1") (pin "1") (pinfunction "1_1") (pintype "passive"))
      (node (ref "R5B1") (pin "1") (pinfunction "1_1") (pintype "passive"))
      (node (ref "X1") (pin "2") (pinfunction "S_2") (pintype "passive"))
    )
    (net (code "18") (name "/IN-PWM-3") (class "Default")
      (node (ref "JP11") (pin "12") (pinfunction "12_12") (pintype "passive"))
      (node (ref "JP4") (pin "3") (pinfunction "3_3") (pintype "passive"))
      (node (ref "R1A2") (pin "2") (pinfunction "2_2") (pintype "passive"))
      (node (ref "R5A2") (pin "1") (pinfunction "1_1") (pintype "passive"))
      (node (ref "X2") (pin "1") (pinfunction "S_1") (pintype "passive"))
    )
    (net (code "19") (name "/IN-PWM-4") (class "Default")
      (node (ref "JP11") (pin "13") (pinfunction "13_13") (pintype "passive"))
      (node (ref "JP4") (pin "1") (pinfunction "1_1") (pintype "passive"))
      (node (ref "R1B2") (pin "1") (pinfunction "1_1") (pintype "passive"))
      (node (ref "R5B2") (pin "1") (pinfunction "1_1") (pintype "passive"))
      (node (ref "X2") (pin "2") (pinfunction "S_2") (pintype "passive"))
    )
    (net (code "20") (name "/ISO-1-5V") (class "Default")
      (node (ref "C11") (pin "1") (pinfunction "1_1") (pintype "passive"))
      (node (ref "JP13") (pin "1") (pinfunction "1_1") (pintype "passive"))
      (node (ref "PS1") (pin "4") (pinfunction "+VOUT_4") (pintype "output"))
      (node (ref "R14") (pin "6") (pinfunction "2_6") (pintype "passive"))
      (node (ref "R14") (pin "7") (pinfunction "2_7") (pintype "passive"))
      (node (ref "X8") (pin "8") (pinfunction "VCC2_8") (pintype "power_in"))
    )
    (net (code "21") (name "/ISO-2-5V") (class "Default")
      (node (ref "C13") (pin "1") (pinfunction "1_1") (pintype "passive"))
      (node (ref "JP15") (pin "1") (pinfunction "1_1") (pintype "passive"))
      (node (ref "PS2") (pin "4") (pinfunction "+VOUT_4") (pintype "output"))
      (node (ref "R16") (pin "6") (pinfunction "2_6") (pintype "passive"))
      (node (ref "R16") (pin "7") (pinfunction "2_7") (pintype "passive"))
      (node (ref "X10") (pin "8") (pinfunction "VCC2_8") (pintype "power_in"))
    )
    (net (code "22") (name "/ISO-3-5V") (class "Default")
      (node (ref "C15") (pin "1") (pinfunction "1_1") (pintype "passive"))
      (node (ref "JP17") (pin "1") (pinfunction "1_1") (pintype "passive"))
      (node (ref "PS3") (pin "4") (pinfunction "+VOUT_4") (pintype "output"))
      (node (ref "R18") (pin "6") (pinfunction "2_6") (pintype "passive"))
      (node (ref "R18") (pin "7") (pinfunction "2_7") (pintype "passive"))
      (node (ref "X12") (pin "8") (pinfunction "VCC2_8") (pintype "power_in"))
    )
    (net (code "23") (name "/ISO-4-5V") (class "Default")
      (node (ref "C17") (pin "1") (pinfunction "1_1") (pintype "passive"))
      (node (ref "JP19") (pin "1") (pinfunction "1_1") (pintype "passive"))
      (node (ref "PS4") (pin "4") (pinfunction "+VOUT_4") (pintype "output"))
      (node (ref "R21") (pin "6") (pinfunction "2_6") (pintype "passive"))
      (node (ref "R21") (pin "7") (pinfunction "2_7") (pintype "passive"))
      (node (ref "X15") (pin "8") (pinfunction "VCC2_8") (pintype "power_in"))
    )
    (net (code "24") (name "/ISO-GND-1") (class "Default")
      (node (ref "C11") (pin "2") (pinfunction "2_2") (pintype "passive"))
      (node (ref "JP12") (pin "3") (pinfunction "3_3") (pintype "passive"))
      (node (ref "PS1") (pin "3") (pinfunction "-VOUT_3") (pintype "output"))
      (node (ref "X8") (pin "5") (pinfunction "GND2_5") (pintype "power_in"))
    )
    (net (code "25") (name "/ISO-GND-2") (class "Default")
      (node (ref "C13") (pin "2") (pinfunction "2_2") (pintype "passive"))
      (node (ref "JP14") (pin "3") (pinfunction "3_3") (pintype "passive"))
      (node (ref "PS2") (pin "3") (pinfunction "-VOUT_3") (pintype "output"))
      (node (ref "X10") (pin "5") (pinfunction "GND2_5") (pintype "power_in"))
    )
    (net (code "26") (name "/ISO-GND-3") (class "Default")
      (node (ref "C15") (pin "2") (pinfunction "2_2") (pintype "passive"))
      (node (ref "JP16") (pin "3") (pinfunction "3_3") (pintype "passive"))
      (node (ref "PS3") (pin "3") (pinfunction "-VOUT_3") (pintype "output"))
      (node (ref "X12") (pin "5") (pinfunction "GND2_5") (pintype "power_in"))
    )
    (net (code "27") (name "/ISO-GND-4") (class "Default")
      (node (ref "C17") (pin "2") (pinfunction "2_2") (pintype "passive"))
      (node (ref "JP18") (pin "3") (pinfunction "3_3") (pintype "passive"))
      (node (ref "PS4") (pin "3") (pinfunction "-VOUT_3") (pintype "output"))
      (node (ref "X15") (pin "5") (pinfunction "GND2_5") (pintype "power_in"))
    )
    (net (code "28") (name "/LED1") (class "Default")
      (node (ref "JP4") (pin "2") (pinfunction "2_2") (pintype "passive"))
      (node (ref "R7") (pin "1") (pinfunction "1_1") (pintype "passive"))
      (node (ref "U1") (pin "25") (pinfunction "GPA4_25") (pintype "bidirectional"))
    )
    (net (code "29") (name "/LED2") (class "Default")
      (node (ref "JP4") (pin "4") (pinfunction "4_4") (pintype "passive"))
      (node (ref "R7") (pin "2") (pinfunction "1_2") (pintype "passive"))
      (node (ref "U1") (pin "26") (pinfunction "GPA5_26") (pintype "bidirectional"))
    )
    (net (code "30") (name "/LED3") (class "Default")
      (node (ref "JP4") (pin "6") (pinfunction "6_6") (pintype "passive"))
      (node (ref "R7") (pin "3") (pinfunction "1_3") (pintype "passive"))
      (node (ref "U1") (pin "27") (pinfunction "GPA6_27") (pintype "bidirectional"))
    )
    (net (code "31") (name "/LED4") (class "Default")
      (node (ref "JP4") (pin "8") (pinfunction "8_8") (pintype "passive"))
      (node (ref "R7") (pin "4") (pinfunction "1_4") (pintype "passive"))
      (node (ref "U1") (pin "28") (pinfunction "GPA7_28") (pintype "bidirectional"))
    )
    (net (code "32") (name "/SCL") (class "Default")
      (node (ref "J2") (pin "3") (pinfunction "3_3") (pintype "passive"))
      (node (ref "J3") (pin "3") (pinfunction "3_3") (pintype "passive"))
      (node (ref "J4") (pin "4") (pinfunction "4_4") (pintype "passive"))
      (node (ref "J5") (pin "4") (pinfunction "4_4") (pintype "passive"))
      (node (ref "J6") (pin "4") (pinfunction "4_4") (pintype "passive"))
      (node (ref "J7") (pin "4") (pinfunction "4_4") (pintype "passive"))
      (node (ref "JP11") (pin "5") (pinfunction "5_5") (pintype "passive"))
      (node (ref "JP5") (pin "1") (pinfunction "1_1") (pintype "passive"))
      (node (ref "JP7") (pin "1") (pinfunction "1_1") (pintype "passive"))
      (node (ref "JP9") (pin "1") (pinfunction "1_1") (pintype "passive"))
      (node (ref "R12") (pin "3") (pinfunction "1_3") (pintype "passive"))
      (node (ref "R13") (pin "3") (pinfunction "1_3") (pintype "passive"))
      (node (ref "R17") (pin "3") (pinfunction "1_3") (pintype "passive"))
      (node (ref "R20") (pin "3") (pinfunction "1_3") (pintype "passive"))
      (node (ref "U1") (pin "12") (pinfunction "SCK_12") (pintype "input"))
      (node (ref "X10") (pin "3") (pinfunction "SCL1_3") (pintype "bidirectional"))
      (node (ref "X12") (pin "3") (pinfunction "SCL1_3") (pintype "bidirectional"))
      (node (ref "X13") (pin "8") (pinfunction "8_8") (pintype "passive"))
      (node (ref "X15") (pin "3") (pinfunction "SCL1_3") (pintype "bidirectional"))
      (node (ref "X16") (pin "8") (pinfunction "8_8") (pintype "passive"))
      (node (ref "X3") (pin "1") (pinfunction "S_1") (pintype "passive"))
      (node (ref "X8") (pin "3") (pinfunction "SCL1_3") (pintype "bidirectional"))
      (node (ref "X9") (pin "8") (pinfunction "8_8") (pintype "passive"))
    )
    (net (code "33") (name "/SCL2") (class "Default")
      (node (ref "JP12") (pin "1") (pinfunction "1_1") (pintype "passive"))
      (node (ref "R14") (pin "3") (pinfunction "1_3") (pintype "passive"))
      (node (ref "X8") (pin "6") (pinfunction "SCL2_6") (pintype "bidirectional"))
    )
    (net (code "34") (name "/SCL3") (class "Default")
      (node (ref "JP14") (pin "1") (pinfunction "1_1") (pintype "passive"))
      (node (ref "R16") (pin "3") (pinfunction "1_3") (pintype "passive"))
      (node (ref "X10") (pin "6") (pinfunction "SCL2_6") (pintype "bidirectional"))
    )
    (net (code "35") (name "/SCL4") (class "Default")
      (node (ref "JP16") (pin "1") (pinfunction "1_1") (pintype "passive"))
      (node (ref "R18") (pin "3") (pinfunction "1_3") (pintype "passive"))
      (node (ref "X12") (pin "6") (pinfunction "SCL2_6") (pintype "bidirectional"))
    )
    (net (code "36") (name "/SCL5") (class "Default")
      (node (ref "JP18") (pin "1") (pinfunction "1_1") (pintype "passive"))
      (node (ref "R21") (pin "3") (pinfunction "1_3") (pintype "passive"))
      (node (ref "X15") (pin "6") (pinfunction "SCL2_6") (pintype "bidirectional"))
    )
    (net (code "37") (name "/SDA") (class "Default")
      (node (ref "J2") (pin "4") (pinfunction "4_4") (pintype "passive"))
      (node (ref "J3") (pin "4") (pinfunction "4_4") (pintype "passive"))
      (node (ref "J4") (pin "3") (pinfunction "3_3") (pintype "passive"))
      (node (ref "J5") (pin "3") (pinfunction "3_3") (pintype "passive"))
      (node (ref "J6") (pin "3") (pinfunction "3_3") (pintype "passive"))
      (node (ref "J7") (pin "3") (pinfunction "3_3") (pintype "passive"))
      (node (ref "JP11") (pin "3") (pinfunction "3_3") (pintype "passive"))
      (node (ref "JP5") (pin "2") (pinfunction "2_2") (pintype "passive"))
      (node (ref "JP7") (pin "2") (pinfunction "2_2") (pintype "passive"))
      (node (ref "JP9") (pin "2") (pinfunction "2_2") (pintype "passive"))
      (node (ref "R12") (pin "2") (pinfunction "1_2") (pintype "passive"))
      (node (ref "R13") (pin "2") (pinfunction "1_2") (pintype "passive"))
      (node (ref "R17") (pin "2") (pinfunction "1_2") (pintype "passive"))
      (node (ref "R20") (pin "2") (pinfunction "1_2") (pintype "passive"))
      (node (ref "U1") (pin "13") (pinfunction "SDA_13") (pintype "bidirectional"))
      (node (ref "X10") (pin "2") (pinfunction "SDA1_2") (pintype "bidirectional"))
      (node (ref "X12") (pin "2") (pinfunction "SDA1_2") (pintype "bidirectional"))
      (node (ref "X13") (pin "6") (pinfunction "6_6") (pintype "passive"))
      (node (ref "X15") (pin "2") (pinfunction "SDA1_2") (pintype "bidirectional"))
      (node (ref "X16") (pin "6") (pinfunction "6_6") (pintype "passive"))
      (node (ref "X3") (pin "2") (pinfunction "S_2") (pintype "passive"))
      (node (ref "X8") (pin "2") (pinfunction "SDA1_2") (pintype "bidirectional"))
      (node (ref "X9") (pin "6") (pinfunction "6_6") (pintype "passive"))
    )
    (net (code "38") (name "/SDA2") (class "Default")
      (node (ref "JP12") (pin "2") (pinfunction "2_2") (pintype "passive"))
      (node (ref "R14") (pin "2") (pinfunction "1_2") (pintype "passive"))
      (node (ref "X8") (pin "7") (pinfunction "SDA2_7") (pintype "bidirectional"))
    )
    (net (code "39") (name "/SDA3") (class "Default")
      (node (ref "JP14") (pin "2") (pinfunction "2_2") (pintype "passive"))
      (node (ref "R16") (pin "2") (pinfunction "1_2") (pintype "passive"))
      (node (ref "X10") (pin "7") (pinfunction "SDA2_7") (pintype "bidirectional"))
    )
    (net (code "40") (name "/SDA4") (class "Default")
      (node (ref "JP16") (pin "2") (pinfunction "2_2") (pintype "passive"))
      (node (ref "R18") (pin "2") (pinfunction "1_2") (pintype "passive"))
      (node (ref "X12") (pin "7") (pinfunction "SDA2_7") (pintype "bidirectional"))
    )
    (net (code "41") (name "/SDA5") (class "Default")
      (node (ref "JP18") (pin "2") (pinfunction "2_2") (pintype "passive"))
      (node (ref "R21") (pin "2") (pinfunction "1_2") (pintype "passive"))
      (node (ref "X15") (pin "7") (pinfunction "SDA2_7") (pintype "bidirectional"))
    )
    (net (code "42") (name "GND") (class "Default")
      (node (ref "C1") (pin "-") (pinfunction "-_-") (pintype "passive"))
      (node (ref "C10") (pin "2") (pinfunction "2_2") (pintype "passive"))
      (node (ref "C12") (pin "2") (pinfunction "2_2") (pintype "passive"))
      (node (ref "C14") (pin "2") (pinfunction "2_2") (pintype "passive"))
      (node (ref "C16") (pin "2") (pinfunction "2_2") (pintype "passive"))
      (node (ref "C1A1") (pin "-") (pinfunction "-_-") (pintype "passive"))
      (node (ref "C1A2") (pin "-") (pinfunction "-_-") (pintype "passive"))
      (node (ref "C1B1") (pin "-") (pinfunction "-_-") (pintype "passive"))
      (node (ref "C1B2") (pin "-") (pinfunction "-_-") (pintype "passive"))
      (node (ref "C2") (pin "1") (pinfunction "1_1") (pintype "passive"))
      (node (ref "C3") (pin "-") (pinfunction "-_-") (pintype "passive"))
      (node (ref "C4") (pin "-") (pinfunction "-_-") (pintype "passive"))
      (node (ref "C5") (pin "-") (pinfunction "-_-") (pintype "passive"))
      (node (ref "C6") (pin "1") (pinfunction "1_1") (pintype "passive"))
      (node (ref "C7") (pin "-") (pinfunction "-_-") (pintype "passive"))
      (node (ref "C8") (pin "-") (pinfunction "-_-") (pintype "passive"))
      (node (ref "C9") (pin "-") (pinfunction "-_-") (pintype "passive"))
      (node (ref "D10") (pin "A") (pinfunction "A_A") (pintype "passive"))
      (node (ref "D17") (pin "A") (pinfunction "A_A") (pintype "passive"))
      (node (ref "D18") (pin "A") (pinfunction "A_A") (pintype "passive"))
      (node (ref "D19") (pin "A") (pinfunction "A_A") (pintype "passive"))
      (node (ref "D20") (pin "A") (pinfunction "A_A") (pintype "passive"))
      (node (ref "D22") (pin "A") (pinfunction "A_A") (pintype "passive"))
      (node (ref "D24") (pin "A") (pinfunction "A_A") (pintype "passive"))
      (node (ref "D26") (pin "A") (pinfunction "A_A") (pintype "passive"))
      (node (ref "D28") (pin "A") (pinfunction "A_A") (pintype "passive"))
      (node (ref "D4") (pin "A") (pinfunction "A_A") (pintype "passive"))
      (node (ref "D6") (pin "A") (pinfunction "A_A") (pintype "passive"))
      (node (ref "D8") (pin "A") (pinfunction "A_A") (pintype "passive"))
      (node (ref "IC2") (pin "8") (pinfunction "GND_8") (pintype "power_in"))
      (node (ref "IC4") (pin "8") (pinfunction "GND_8") (pintype "power_in"))
      (node (ref "IC5") (pin "8") (pinfunction "GND_8") (pintype "power_in"))
      (node (ref "J1") (pin "2") (pinfunction "2_2") (pintype "passive"))
      (node (ref "J1") (pin "3") (pinfunction "3_3") (pintype "passive"))
      (node (ref "J2") (pin "2") (pinfunction "2_2") (pintype "power_in"))
      (node (ref "J3") (pin "1") (pinfunction "1_1") (pintype "power_in"))
      (node (ref "J4") (pin "1") (pinfunction "1_1") (pintype "power_in"))
      (node (ref "J5") (pin "1") (pinfunction "1_1") (pintype "power_in"))
      (node (ref "J6") (pin "1") (pinfunction "1_1") (pintype "power_in"))
      (node (ref "J7") (pin "1") (pinfunction "1_1") (pintype "power_in"))
      (node (ref "JP1") (pin "1") (pinfunction "1_1") (pintype "passive"))
      (node (ref "JP11") (pin "14") (pinfunction "14_14") (pintype "passive"))
      (node (ref "JP11") (pin "6") (pinfunction "6_6") (pintype "passive"))
      (node (ref "JP11") (pin "9") (pinfunction "9_9") (pintype "passive"))
      (node (ref "JP2") (pin "1") (pinfunction "1_1") (pintype "passive"))
      (node (ref "JP3") (pin "1") (pinfunction "1_1") (pintype "passive"))
      (node (ref "JP5") (pin "3") (pinfunction "3_3") (pintype "passive"))
      (node (ref "JP7") (pin "3") (pinfunction "3_3") (pintype "passive"))
      (node (ref "JP9") (pin "3") (pinfunction "3_3") (pintype "passive"))
      (node (ref "LED1") (pin "C") (pinfunction "C_C") (pintype "passive"))
      (node (ref "LED10") (pin "C") (pinfunction "C_C") (pintype "passive"))
      (node (ref "LED11") (pin "C") (pinfunction "C_C") (pintype "passive"))
      (node (ref "LED12") (pin "C") (pinfunction "C_C") (pintype "passive"))
      (node (ref "LED13") (pin "C") (pinfunction "C_C") (pintype "passive"))
      (node (ref "LED14") (pin "C") (pinfunction "C_C") (pintype "passive"))
      (node (ref "LED15") (pin "C") (pinfunction "C_C") (pintype "passive"))
      (node (ref "LED16") (pin "C") (pinfunction "C_C") (pintype "passive"))
      (node (ref "LED2") (pin "C") (pinfunction "C_C") (pintype "passive"))
      (node (ref "LED3") (pin "C") (pinfunction "C_C") (pintype "passive"))
      (node (ref "LED4") (pin "C") (pinfunction "C_C") (pintype "passive"))
      (node (ref "LED5") (pin "C") (pinfunction "C_C") (pintype "passive"))
      (node (ref "LED6") (pin "C") (pinfunction "C_C") (pintype "passive"))
      (node (ref "LED7") (pin "C") (pinfunction "C_C") (pintype "passive"))
      (node (ref "LED8") (pin "C") (pinfunction "C_C") (pintype "passive"))
      (node (ref "LED9") (pin "C") (pinfunction "C_C") (pintype "passive"))
      (node (ref "PS1") (pin "1") (pinfunction "-VIN_1") (pintype "input"))
      (node (ref "PS2") (pin "1") (pinfunction "-VIN_1") (pintype "input"))
      (node (ref "PS3") (pin "1") (pinfunction "-VIN_1") (pintype "input"))
      (node (ref "PS4") (pin "1") (pinfunction "-VIN_1") (pintype "input"))
      (node (ref "R1") (pin "1") (pinfunction "1_1") (pintype "passive"))
      (node (ref "R10") (pin "1") (pinfunction "1_1") (pintype "passive"))
      (node (ref "R11") (pin "1") (pinfunction "1_1") (pintype "passive"))
      (node (ref "R2A1") (pin "1") (pinfunction "1_1") (pintype "passive"))
      (node (ref "R2A2") (pin "1") (pinfunction "1_1") (pintype "passive"))
      (node (ref "R2B1") (pin "2") (pinfunction "2_2") (pintype "passive"))
      (node (ref "R2B2") (pin "2") (pinfunction "2_2") (pintype "passive"))
      (node (ref "R4") (pin "1") (pinfunction "1_1") (pintype "passive"))
      (node (ref "R5") (pin "1") (pinfunction "1_1") (pintype "passive"))
      (node (ref "R5A1") (pin "2") (pinfunction "2_2") (pintype "passive"))
      (node (ref "R5A2") (pin "2") (pinfunction "2_2") (pintype "passive"))
      (node (ref "R5B1") (pin "2") (pinfunction "2_2") (pintype "passive"))
      (node (ref "R5B2") (pin "2") (pinfunction "2_2") (pintype "passive"))
      (node (ref "R6") (pin "1") (pinfunction "1_1") (pintype "passive"))
      (node (ref "R8") (pin "1") (pinfunction "1_1") (pintype "passive"))
      (node (ref "R9") (pin "1") (pinfunction "1_1") (pintype "passive"))
      (node (ref "U1") (pin "10") (pinfunction "VSS_10") (pintype "power_in"))
      (node (ref "U2") (pin "4") (pinfunction "P$V-_4") (pintype "bidirectional"))
      (node (ref "U3") (pin "4") (pinfunction "P$V-_4") (pintype "bidirectional"))
      (node (ref "X10") (pin "4") (pinfunction "GND1_4") (pintype "power_in"))
      (node (ref "X12") (pin "4") (pinfunction "GND1_4") (pintype "power_in"))
      (node (ref "X13") (pin "2") (pinfunction "2_2") (pintype "passive"))
      (node (ref "X15") (pin "4") (pinfunction "GND1_4") (pintype "power_in"))
      (node (ref "X16") (pin "2") (pinfunction "2_2") (pintype "passive"))
      (node (ref "X4") (pin "2") (pinfunction "S_2") (pintype "passive"))
      (node (ref "X5") (pin "2") (pinfunction "S_2") (pintype "passive"))
      (node (ref "X6") (pin "2") (pinfunction "S_2") (pintype "passive"))
      (node (ref "X7") (pin "2") (pinfunction "S_2") (pintype "passive"))
      (node (ref "X8") (pin "4") (pinfunction "GND1_4") (pintype "power_in"))
      (node (ref "X9") (pin "2") (pinfunction "2_2") (pintype "passive"))
    )
    (net (code "43") (name "Net-(C1A1-Pad+)") (class "Default")
      (node (ref "C1A1") (pin "+") (pinfunction "+_+") (pintype "passive"))
      (node (ref "R1A1") (pin "1") (pinfunction "1_1") (pintype "passive"))
      (node (ref "R4A2") (pin "1") (pinfunction "1_1") (pintype "passive"))
    )
    (net (code "44") (name "Net-(C1A2-Pad+)") (class "Default")
      (node (ref "C1A2") (pin "+") (pinfunction "+_+") (pintype "passive"))
      (node (ref "R1A2") (pin "1") (pinfunction "1_1") (pintype "passive"))
      (node (ref "R4A1") (pin "1") (pinfunction "1_1") (pintype "passive"))
    )
    (net (code "45") (name "Net-(C1B1-Pad+)") (class "Default")
      (node (ref "C1B1") (pin "+") (pinfunction "+_+") (pintype "passive"))
      (node (ref "R1B1") (pin "2") (pinfunction "2_2") (pintype "passive"))
      (node (ref "R4B1") (pin "1") (pinfunction "1_1") (pintype "passive"))
    )
    (net (code "46") (name "Net-(C1B2-Pad+)") (class "Default")
      (node (ref "C1B2") (pin "+") (pinfunction "+_+") (pintype "passive"))
      (node (ref "R1B2") (pin "2") (pinfunction "2_2") (pintype "passive"))
      (node (ref "R4B2") (pin "1") (pinfunction "1_1") (pintype "passive"))
    )
    (net (code "47") (name "Net-(IC1-ADJ)") (class "Default")
      (node (ref "C4") (pin "+") (pinfunction "+_+") (pintype "passive"))
      (node (ref "D1") (pin "A") (pinfunction "A_A") (pintype "passive"))
      (node (ref "IC1") (pin "1") (pinfunction "ADJ_1") (pintype "input"))
      (node (ref "R2") (pin "1") (pinfunction "1_1") (pintype "passive"))
      (node (ref "R4") (pin "2") (pinfunction "2_2") (pintype "passive"))
    )
    (net (code "48") (name "Net-(IC2-OUT1)") (class "Default")
      (node (ref "D3") (pin "A") (pinfunction "A_A") (pintype "passive"))
      (node (ref "D4") (pin "C") (pinfunction "C_C") (pintype "passive"))
      (node (ref "IC2") (pin "2") (pinfunction "OUT1_2") (pintype "output"))
      (node (ref "R15") (pin "1") (pinfunction "1_1") (pintype "passive"))
      (node (ref "X9") (pin "1") (pinfunction "1_1") (pintype "passive"))
    )
    (net (code "49") (name "Net-(IC2-OUT2)") (class "Default")
      (node (ref "D5") (pin "A") (pinfunction "A_A") (pintype "passive"))
      (node (ref "D6") (pin "C") (pinfunction "C_C") (pintype "passive"))
      (node (ref "IC2") (pin "3") (pinfunction "OUT2_3") (pintype "output"))
      (node (ref "R15") (pin "2") (pinfunction "1_2") (pintype "passive"))
      (node (ref "X9") (pin "3") (pinfunction "3_3") (pintype "passive"))
    )
    (net (code "50") (name "Net-(IC2-OUT3)") (class "Default")
      (node (ref "D7") (pin "A") (pinfunction "A_A") (pintype "passive"))
      (node (ref "D8") (pin "C") (pinfunction "C_C") (pintype "passive"))
      (node (ref "IC2") (pin "13") (pinfunction "OUT3_13") (pintype "output"))
      (node (ref "R15") (pin "3") (pinfunction "1_3") (pintype "passive"))
      (node (ref "X9") (pin "5") (pinfunction "5_5") (pintype "passive"))
    )
    (net (code "51") (name "Net-(IC2-OUT4)") (class "Default")
      (node (ref "D10") (pin "C") (pinfunction "C_C") (pintype "passive"))
      (node (ref "D9") (pin "A") (pinfunction "A_A") (pintype "passive"))
      (node (ref "IC2") (pin "14") (pinfunction "OUT4_14") (pintype "output"))
      (node (ref "R15") (pin "4") (pinfunction "1_4") (pintype "passive"))
      (node (ref "X9") (pin "7") (pinfunction "7_7") (pintype "passive"))
    )
    (net (code "52") (name "Net-(IC2-SEN_A)") (class "Default")
      (node (ref "IC2") (pin "1") (pinfunction "SEN_A_1") (pintype "input"))
      (node (ref "R1") (pin "2") (pinfunction "2_2") (pintype "passive"))
    )
    (net (code "53") (name "Net-(IC2-SEN_B)") (class "Default")
      (node (ref "IC2") (pin "15") (pinfunction "SEN_B_15") (pintype "input"))
      (node (ref "R6") (pin "2") (pinfunction "2_2") (pintype "passive"))
    )
    (net (code "54") (name "Net-(IC3-ADJ)") (class "Default")
      (node (ref "C8") (pin "+") (pinfunction "+_+") (pintype "passive"))
      (node (ref "D11") (pin "A") (pinfunction "A_A") (pintype "passive"))
      (node (ref "IC3") (pin "1") (pinfunction "ADJ_1") (pintype "input"))
      (node (ref "R3") (pin "1") (pinfunction "1_1") (pintype "passive"))
      (node (ref "R5") (pin "2") (pinfunction "2_2") (pintype "passive"))
    )
    (net (code "55") (name "Net-(IC4-OUT1)") (class "Default")
      (node (ref "D13") (pin "A") (pinfunction "A_A") (pintype "passive"))
      (node (ref "D17") (pin "C") (pinfunction "C_C") (pintype "passive"))
      (node (ref "IC4") (pin "2") (pinfunction "OUT1_2") (pintype "output"))
      (node (ref "R19") (pin "1") (pinfunction "1_1") (pintype "passive"))
      (node (ref "X13") (pin "1") (pinfunction "1_1") (pintype "passive"))
    )
    (net (code "56") (name "Net-(IC4-OUT2)") (class "Default")
      (node (ref "D14") (pin "A") (pinfunction "A_A") (pintype "passive"))
      (node (ref "D18") (pin "C") (pinfunction "C_C") (pintype "passive"))
      (node (ref "IC4") (pin "3") (pinfunction "OUT2_3") (pintype "output"))
      (node (ref "R19") (pin "2") (pinfunction "1_2") (pintype "passive"))
      (node (ref "X13") (pin "3") (pinfunction "3_3") (pintype "passive"))
    )
    (net (code "57") (name "Net-(IC4-OUT3)") (class "Default")
      (node (ref "D15") (pin "A") (pinfunction "A_A") (pintype "passive"))
      (node (ref "D19") (pin "C") (pinfunction "C_C") (pintype "passive"))
      (node (ref "IC4") (pin "13") (pinfunction "OUT3_13") (pintype "output"))
      (node (ref "R19") (pin "3") (pinfunction "1_3") (pintype "passive"))
      (node (ref "X13") (pin "5") (pinfunction "5_5") (pintype "passive"))
    )
    (net (code "58") (name "Net-(IC4-OUT4)") (class "Default")
      (node (ref "D16") (pin "A") (pinfunction "A_A") (pintype "passive"))
      (node (ref "D20") (pin "C") (pinfunction "C_C") (pintype "passive"))
      (node (ref "IC4") (pin "14") (pinfunction "OUT4_14") (pintype "output"))
      (node (ref "R19") (pin "4") (pinfunction "1_4") (pintype "passive"))
      (node (ref "X13") (pin "7") (pinfunction "7_7") (pintype "passive"))
    )
    (net (code "59") (name "Net-(IC4-SEN_A)") (class "Default")
      (node (ref "IC4") (pin "1") (pinfunction "SEN_A_1") (pintype "input"))
      (node (ref "R9") (pin "2") (pinfunction "2_2") (pintype "passive"))
    )
    (net (code "60") (name "Net-(IC4-SEN_B)") (class "Default")
      (node (ref "IC4") (pin "15") (pinfunction "SEN_B_15") (pintype "input"))
      (node (ref "R8") (pin "2") (pinfunction "2_2") (pintype "passive"))
    )
    (net (code "61") (name "Net-(IC5-OUT1)") (class "Default")
      (node (ref "D21") (pin "A") (pinfunction "A_A") (pintype "passive"))
      (node (ref "D22") (pin "C") (pinfunction "C_C") (pintype "passive"))
      (node (ref "IC5") (pin "2") (pinfunction "OUT1_2") (pintype "output"))
      (node (ref "R22") (pin "1") (pinfunction "1_1") (pintype "passive"))
      (node (ref "X16") (pin "1") (pinfunction "1_1") (pintype "passive"))
    )
    (net (code "62") (name "Net-(IC5-OUT2)") (class "Default")
      (node (ref "D23") (pin "A") (pinfunction "A_A") (pintype "passive"))
      (node (ref "D24") (pin "C") (pinfunction "C_C") (pintype "passive"))
      (node (ref "IC5") (pin "3") (pinfunction "OUT2_3") (pintype "output"))
      (node (ref "R22") (pin "2") (pinfunction "1_2") (pintype "passive"))
      (node (ref "X16") (pin "3") (pinfunction "3_3") (pintype "passive"))
    )
    (net (code "63") (name "Net-(IC5-OUT3)") (class "Default")
      (node (ref "D25") (pin "A") (pinfunction "A_A") (pintype "passive"))
      (node (ref "D26") (pin "C") (pinfunction "C_C") (pintype "passive"))
      (node (ref "IC5") (pin "13") (pinfunction "OUT3_13") (pintype "output"))
      (node (ref "R22") (pin "3") (pinfunction "1_3") (pintype "passive"))
      (node (ref "X16") (pin "5") (pinfunction "5_5") (pintype "passive"))
    )
    (net (code "64") (name "Net-(IC5-OUT4)") (class "Default")
      (node (ref "D27") (pin "A") (pinfunction "A_A") (pintype "passive"))
      (node (ref "D28") (pin "C") (pinfunction "C_C") (pintype "passive"))
      (node (ref "IC5") (pin "14") (pinfunction "OUT4_14") (pintype "output"))
      (node (ref "R22") (pin "4") (pinfunction "1_4") (pintype "passive"))
      (node (ref "X16") (pin "7") (pinfunction "7_7") (pintype "passive"))
    )
    (net (code "65") (name "Net-(IC5-SEN_A)") (class "Default")
      (node (ref "IC5") (pin "1") (pinfunction "SEN_A_1") (pintype "input"))
      (node (ref "R11") (pin "2") (pinfunction "2_2") (pintype "passive"))
    )
    (net (code "66") (name "Net-(IC5-SEN_B)") (class "Default")
      (node (ref "IC5") (pin "15") (pinfunction "SEN_B_15") (pintype "input"))
      (node (ref "R10") (pin "2") (pinfunction "2_2") (pintype "passive"))
    )
    (net (code "67") (name "Net-(JP13-Pad2)") (class "Default")
      (node (ref "JP13") (pin "2") (pinfunction "2_2") (pintype "passive"))
      (node (ref "X18") (pin "1") (pinfunction "1_1") (pintype "passive"))
    )
    (net (code "68") (name "Net-(JP13-Pad3)") (class "Default")
      (node (ref "JP13") (pin "3") (pinfunction "3_3") (pintype "passive"))
      (node (ref "X18") (pin "2") (pinfunction "2_2") (pintype "passive"))
      (node (ref "X18") (pin "3") (pinfunction "2_3") (pintype "passive"))
      (node (ref "X18") (pin "4") (pinfunction "2_4") (pintype "passive"))
      (node (ref "X18") (pin "5") (pinfunction "2_5") (pintype "passive"))
    )
    (net (code "69") (name "Net-(JP15-Pad2)") (class "Default")
      (node (ref "JP15") (pin "2") (pinfunction "2_2") (pintype "passive"))
      (node (ref "X19") (pin "1") (pinfunction "1_1") (pintype "passive"))
    )
    (net (code "70") (name "Net-(JP15-Pad3)") (class "Default")
      (node (ref "JP15") (pin "3") (pinfunction "3_3") (pintype "passive"))
      (node (ref "X19") (pin "2") (pinfunction "2_2") (pintype "passive"))
      (node (ref "X19") (pin "3") (pinfunction "2_3") (pintype "passive"))
      (node (ref "X19") (pin "4") (pinfunction "2_4") (pintype "passive"))
      (node (ref "X19") (pin "5") (pinfunction "2_5") (pintype "passive"))
    )
    (net (code "71") (name "Net-(JP17-Pad2)") (class "Default")
      (node (ref "JP17") (pin "2") (pinfunction "2_2") (pintype "passive"))
      (node (ref "X20") (pin "1") (pinfunction "1_1") (pintype "passive"))
    )
    (net (code "72") (name "Net-(JP17-Pad3)") (class "Default")
      (node (ref "JP17") (pin "3") (pinfunction "3_3") (pintype "passive"))
      (node (ref "X20") (pin "2") (pinfunction "2_2") (pintype "passive"))
      (node (ref "X20") (pin "3") (pinfunction "2_3") (pintype "passive"))
      (node (ref "X20") (pin "4") (pinfunction "2_4") (pintype "passive"))
      (node (ref "X20") (pin "5") (pinfunction "2_5") (pintype "passive"))
    )
    (net (code "73") (name "Net-(JP19-Pad2)") (class "Default")
      (node (ref "JP19") (pin "2") (pinfunction "2_2") (pintype "passive"))
      (node (ref "X21") (pin "1") (pinfunction "1_1") (pintype "passive"))
    )
    (net (code "74") (name "Net-(JP19-Pad3)") (class "Default")
      (node (ref "JP19") (pin "3") (pinfunction "3_3") (pintype "passive"))
      (node (ref "X21") (pin "2") (pinfunction "2_2") (pintype "passive"))
      (node (ref "X21") (pin "3") (pinfunction "2_3") (pintype "passive"))
      (node (ref "X21") (pin "4") (pinfunction "2_4") (pintype "passive"))
      (node (ref "X21") (pin "5") (pinfunction "2_5") (pintype "passive"))
    )
    (net (code "75") (name "Net-(R3-1A1-CCW)") (class "Default")
      (node (ref "R2A1") (pin "2") (pinfunction "2_2") (pintype "passive"))
      (node (ref "R3-1A1") (pin "1") (pinfunction "CCW_1") (pintype "passive"))
      (node (ref "U2") (pin "6") (pinfunction "-IN_6") (pintype "input"))
    )
    (net (code "76") (name "Net-(R3-1A1-CW)") (class "Default")
      (node (ref "R3-1A1") (pin "2") (pinfunction "WIPER_2") (pintype "passive"))
      (node (ref "R3-1A1") (pin "3") (pinfunction "CW_3") (pintype "passive"))
      (node (ref "R3-2A1") (pin "1") (pinfunction "1_1") (pintype "passive"))
    )
    (net (code "77") (name "Net-(R3-1A2-CCW)") (class "Default")
      (node (ref "R2A2") (pin "2") (pinfunction "2_2") (pintype "passive"))
      (node (ref "R3-1A2") (pin "1") (pinfunction "CCW_1") (pintype "passive"))
      (node (ref "U3") (pin "6") (pinfunction "-IN_6") (pintype "input"))
    )
    (net (code "78") (name "Net-(R3-1A2-CW)") (class "Default")
      (node (ref "R3-1A2") (pin "2") (pinfunction "WIPER_2") (pintype "passive"))
      (node (ref "R3-1A2") (pin "3") (pinfunction "CW_3") (pintype "passive"))
      (node (ref "R3-2A2") (pin "1") (pinfunction "1_1") (pintype "passive"))
    )
    (net (code "79") (name "Net-(R3-1B1-CCW)") (class "Default")
      (node (ref "R2B1") (pin "1") (pinfunction "1_1") (pintype "passive"))
      (node (ref "R3-1B1") (pin "1") (pinfunction "CCW_1") (pintype "passive"))
      (node (ref "U2") (pin "2") (pinfunction "-IN_2") (pintype "input"))
    )
    (net (code "80") (name "Net-(R3-1B1-CW)") (class "Default")
      (node (ref "R3-1B1") (pin "2") (pinfunction "WIPER_2") (pintype "passive"))
      (node (ref "R3-1B1") (pin "3") (pinfunction "CW_3") (pintype "passive"))
      (node (ref "R3-2B1") (pin "1") (pinfunction "1_1") (pintype "passive"))
    )
    (net (code "81") (name "Net-(R3-1B2-CCW)") (class "Default")
      (node (ref "R2B2") (pin "1") (pinfunction "1_1") (pintype "passive"))
      (node (ref "R3-1B2") (pin "1") (pinfunction "CCW_1") (pintype "passive"))
      (node (ref "U3") (pin "2") (pinfunction "-IN_2") (pintype "input"))
    )
    (net (code "82") (name "Net-(R3-1B2-CW)") (class "Default")
      (node (ref "R3-1B2") (pin "2") (pinfunction "WIPER_2") (pintype "passive"))
      (node (ref "R3-1B2") (pin "3") (pinfunction "CW_3") (pintype "passive"))
      (node (ref "R3-2B2") (pin "1") (pinfunction "1_1") (pintype "passive"))
    )
    (net (code "83") (name "Net-(R3-2A1-Pad2)") (class "Default")
      (node (ref "R3-2A1") (pin "2") (pinfunction "2_2") (pintype "passive"))
      (node (ref "R3-3A1") (pin "1") (pinfunction "1_1") (pintype "passive"))
    )
    (net (code "84") (name "Net-(R3-2A2-Pad2)") (class "Default")
      (node (ref "R3-2A2") (pin "2") (pinfunction "2_2") (pintype "passive"))
      (node (ref "R3-3A2") (pin "1") (pinfunction "1_1") (pintype "passive"))
    )
    (net (code "85") (name "Net-(R3-2B1-Pad2)") (class "Default")
      (node (ref "R3-2B1") (pin "2") (pinfunction "2_2") (pintype "passive"))
      (node (ref "R3-3B1") (pin "1") (pinfunction "1_1") (pintype "passive"))
    )
    (net (code "86") (name "Net-(R3-2B2-Pad2)") (class "Default")
      (node (ref "R3-2B2") (pin "2") (pinfunction "2_2") (pintype "passive"))
      (node (ref "R3-3B2") (pin "1") (pinfunction "1_1") (pintype "passive"))
    )
    (net (code "87") (name "Net-(R7A-2)") (class "Default")
      (node (ref "LED1") (pin "A") (pinfunction "A_A") (pintype "passive"))
      (node (ref "R7") (pin "8") (pinfunction "2_8") (pintype "passive"))
    )
    (net (code "88") (name "Net-(R7B-2)") (class "Default")
      (node (ref "LED2") (pin "A") (pinfunction "A_A") (pintype "passive"))
      (node (ref "R7") (pin "7") (pinfunction "2_7") (pintype "passive"))
    )
    (net (code "89") (name "Net-(R7C-2)") (class "Default")
      (node (ref "LED3") (pin "A") (pinfunction "A_A") (pintype "passive"))
      (node (ref "R7") (pin "6") (pinfunction "2_6") (pintype "passive"))
    )
    (net (code "90") (name "Net-(R7D-2)") (class "Default")
      (node (ref "LED4") (pin "A") (pinfunction "A_A") (pintype "passive"))
      (node (ref "R7") (pin "5") (pinfunction "2_5") (pintype "passive"))
    )
    (net (code "91") (name "Net-(R15A-2)") (class "Default")
      (node (ref "LED5") (pin "A") (pinfunction "A_A") (pintype "passive"))
      (node (ref "R15") (pin "8") (pinfunction "2_8") (pintype "passive"))
    )
    (net (code "92") (name "Net-(R15B-2)") (class "Default")
      (node (ref "LED6") (pin "A") (pinfunction "A_A") (pintype "passive"))
      (node (ref "R15") (pin "7") (pinfunction "2_7") (pintype "passive"))
    )
    (net (code "93") (name "Net-(R15C-2)") (class "Default")
      (node (ref "LED7") (pin "A") (pinfunction "A_A") (pintype "passive"))
      (node (ref "R15") (pin "6") (pinfunction "2_6") (pintype "passive"))
    )
    (net (code "94") (name "Net-(R15D-2)") (class "Default")
      (node (ref "LED8") (pin "A") (pinfunction "A_A") (pintype "passive"))
      (node (ref "R15") (pin "5") (pinfunction "2_5") (pintype "passive"))
    )
    (net (code "95") (name "Net-(R19A-2)") (class "Default")
      (node (ref "LED9") (pin "A") (pinfunction "A_A") (pintype "passive"))
      (node (ref "R19") (pin "8") (pinfunction "2_8") (pintype "passive"))
    )
    (net (code "96") (name "Net-(R19B-2)") (class "Default")
      (node (ref "LED10") (pin "A") (pinfunction "A_A") (pintype "passive"))
      (node (ref "R19") (pin "7") (pinfunction "2_7") (pintype "passive"))
    )
    (net (code "97") (name "Net-(R19C-2)") (class "Default")
      (node (ref "LED11") (pin "A") (pinfunction "A_A") (pintype "passive"))
      (node (ref "R19") (pin "6") (pinfunction "2_6") (pintype "passive"))
    )
    (net (code "98") (name "Net-(R19D-2)") (class "Default")
      (node (ref "LED12") (pin "A") (pinfunction "A_A") (pintype "passive"))
      (node (ref "R19") (pin "5") (pinfunction "2_5") (pintype "passive"))
    )
    (net (code "99") (name "Net-(R22A-2)") (class "Default")
      (node (ref "LED13") (pin "A") (pinfunction "A_A") (pintype "passive"))
      (node (ref "R22") (pin "8") (pinfunction "2_8") (pintype "passive"))
    )
    (net (code "100") (name "Net-(R22B-2)") (class "Default")
      (node (ref "LED14") (pin "A") (pinfunction "A_A") (pintype "passive"))
      (node (ref "R22") (pin "7") (pinfunction "2_7") (pintype "passive"))
    )
    (net (code "101") (name "Net-(R22C-2)") (class "Default")
      (node (ref "LED15") (pin "A") (pinfunction "A_A") (pintype "passive"))
      (node (ref "R22") (pin "6") (pinfunction "2_6") (pintype "passive"))
    )
    (net (code "102") (name "Net-(R22D-2)") (class "Default")
      (node (ref "LED16") (pin "A") (pinfunction "A_A") (pintype "passive"))
      (node (ref "R22") (pin "5") (pinfunction "2_5") (pintype "passive"))
    )
    (net (code "103") (name "Net-(U1-A0)") (class "Default")
      (node (ref "JP1") (pin "2") (pinfunction "2_2") (pintype "passive"))
      (node (ref "U1") (pin "15") (pinfunction "A0_15") (pintype "input"))
    )
    (net (code "104") (name "Net-(U1-A1)") (class "Default")
      (node (ref "JP2") (pin "2") (pinfunction "2_2") (pintype "passive"))
      (node (ref "U1") (pin "16") (pinfunction "A1_16") (pintype "input"))
    )
    (net (code "105") (name "Net-(U1-A2)") (class "Default")
      (node (ref "JP3") (pin "2") (pinfunction "2_2") (pintype "passive"))
      (node (ref "U1") (pin "17") (pinfunction "A2_17") (pintype "input"))
    )
    (net (code "106") (name "Net-(U2A-+IN)") (class "Default")
      (node (ref "R4B1") (pin "2") (pinfunction "2_2") (pintype "passive"))
      (node (ref "U2") (pin "3") (pinfunction "+IN_3") (pintype "input"))
    )
    (net (code "107") (name "Net-(U2A-OUT)") (class "Default")
      (node (ref "R3-3B1") (pin "2") (pinfunction "2_2") (pintype "passive"))
      (node (ref "U2") (pin "1") (pinfunction "OUT_1") (pintype "output"))
      (node (ref "X5") (pin "1") (pinfunction "S_1") (pintype "passive"))
    )
    (net (code "108") (name "Net-(U2B-+IN)") (class "Default")
      (node (ref "R4A2") (pin "2") (pinfunction "2_2") (pintype "passive"))
      (node (ref "U2") (pin "5") (pinfunction "+IN_5") (pintype "input"))
    )
    (net (code "109") (name "Net-(U2B-OUT)") (class "Default")
      (node (ref "R3-3A1") (pin "2") (pinfunction "2_2") (pintype "passive"))
      (node (ref "U2") (pin "7") (pinfunction "OUT_7") (pintype "output"))
      (node (ref "X4") (pin "1") (pinfunction "S_1") (pintype "passive"))
    )
    (net (code "110") (name "Net-(U3A-+IN)") (class "Default")
      (node (ref "R4B2") (pin "2") (pinfunction "2_2") (pintype "passive"))
      (node (ref "U3") (pin "3") (pinfunction "+IN_3") (pintype "input"))
    )
    (net (code "111") (name "Net-(U3A-OUT)") (class "Default")
      (node (ref "R3-3B2") (pin "2") (pinfunction "2_2") (pintype "passive"))
      (node (ref "U3") (pin "1") (pinfunction "OUT_1") (pintype "output"))
      (node (ref "X7") (pin "1") (pinfunction "S_1") (pintype "passive"))
    )
    (net (code "112") (name "Net-(U3B-+IN)") (class "Default")
      (node (ref "R4A1") (pin "2") (pinfunction "2_2") (pintype "passive"))
      (node (ref "U3") (pin "5") (pinfunction "+IN_5") (pintype "input"))
    )
    (net (code "113") (name "Net-(U3B-OUT)") (class "Default")
      (node (ref "R3-3A2") (pin "2") (pinfunction "2_2") (pintype "passive"))
      (node (ref "U3") (pin "7") (pinfunction "OUT_7") (pintype "output"))
      (node (ref "X6") (pin "1") (pinfunction "S_1") (pintype "passive"))
    )
    (net (code "114") (name "Net-(X11A-S)") (class "Default")
      (node (ref "JP6") (pin "3") (pinfunction "3_3") (pintype "passive"))
      (node (ref "X11") (pin "1") (pinfunction "S_1") (pintype "passive"))
    )
    (net (code "115") (name "Net-(X11B-S)") (class "Default")
      (node (ref "JP6") (pin "2") (pinfunction "2_2") (pintype "passive"))
      (node (ref "X11") (pin "2") (pinfunction "S_2") (pintype "passive"))
    )
    (net (code "116") (name "Net-(X14A-S)") (class "Default")
      (node (ref "JP8") (pin "3") (pinfunction "3_3") (pintype "passive"))
      (node (ref "X14") (pin "1") (pinfunction "S_1") (pintype "passive"))
    )
    (net (code "117") (name "Net-(X14B-S)") (class "Default")
      (node (ref "JP8") (pin "2") (pinfunction "2_2") (pintype "passive"))
      (node (ref "X14") (pin "2") (pinfunction "S_2") (pintype "passive"))
    )
    (net (code "118") (name "Net-(X17A-S)") (class "Default")
      (node (ref "JP10") (pin "3") (pinfunction "3_3") (pintype "passive"))
      (node (ref "X17") (pin "1") (pinfunction "S_1") (pintype "passive"))
    )
    (net (code "119") (name "Net-(X17B-S)") (class "Default")
      (node (ref "JP10") (pin "2") (pinfunction "2_2") (pintype "passive"))
      (node (ref "X17") (pin "2") (pinfunction "S_2") (pintype "passive"))
    )
    (net (code "120") (name "unconnected-(JP11-Pad1)") (class "Default")
      (node (ref "JP11") (pin "1") (pinfunction "1_1") (pintype "passive"))
    )
    (net (code "121") (name "unconnected-(JP11-Pad2)") (class "Default")
      (node (ref "JP11") (pin "2") (pinfunction "2_2") (pintype "passive"))
    )
    (net (code "122") (name "unconnected-(JP11-Pad4)") (class "Default")
      (node (ref "JP11") (pin "4") (pinfunction "4_4") (pintype "passive"))
    )
    (net (code "123") (name "unconnected-(JP11-Pad8)") (class "Default")
      (node (ref "JP11") (pin "8") (pinfunction "8_8") (pintype "passive"))
    )
    (net (code "124") (name "unconnected-(JP11-Pad10)") (class "Default")
      (node (ref "JP11") (pin "10") (pinfunction "10_10") (pintype "passive"))
    )
    (net (code "125") (name "unconnected-(U1-INTA-Pad20)") (class "Default")
      (node (ref "U1") (pin "20") (pinfunction "INTA_20") (pintype "output"))
    )
    (net (code "126") (name "unconnected-(U1-INTB-Pad19)") (class "Default")
      (node (ref "U1") (pin "19") (pinfunction "INTB_19") (pintype "output"))
    )
  )
)
